# AVALON2_chip_21b.net
KiCad netlist of a schematic drawn in Altium Designer
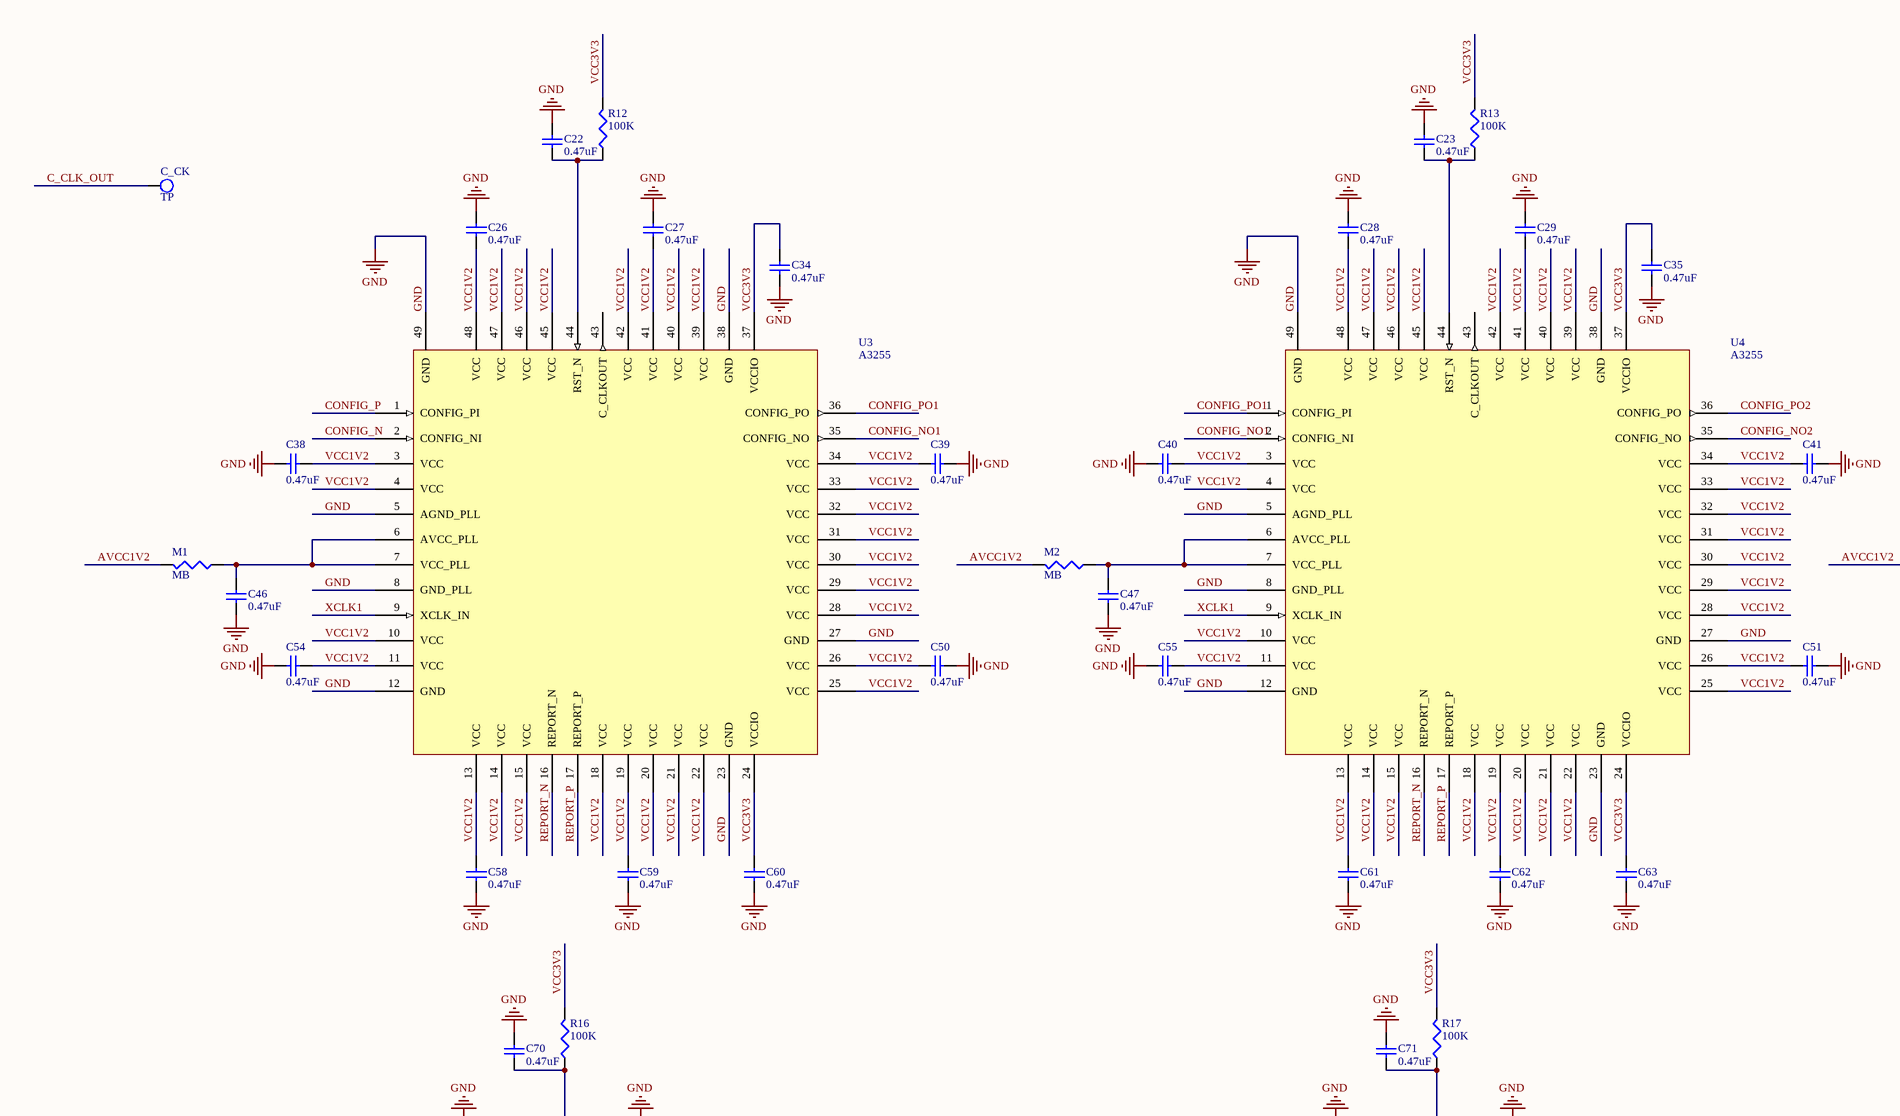
[diagram p0: AVALON2_chip_21b.SchDoc, top left]
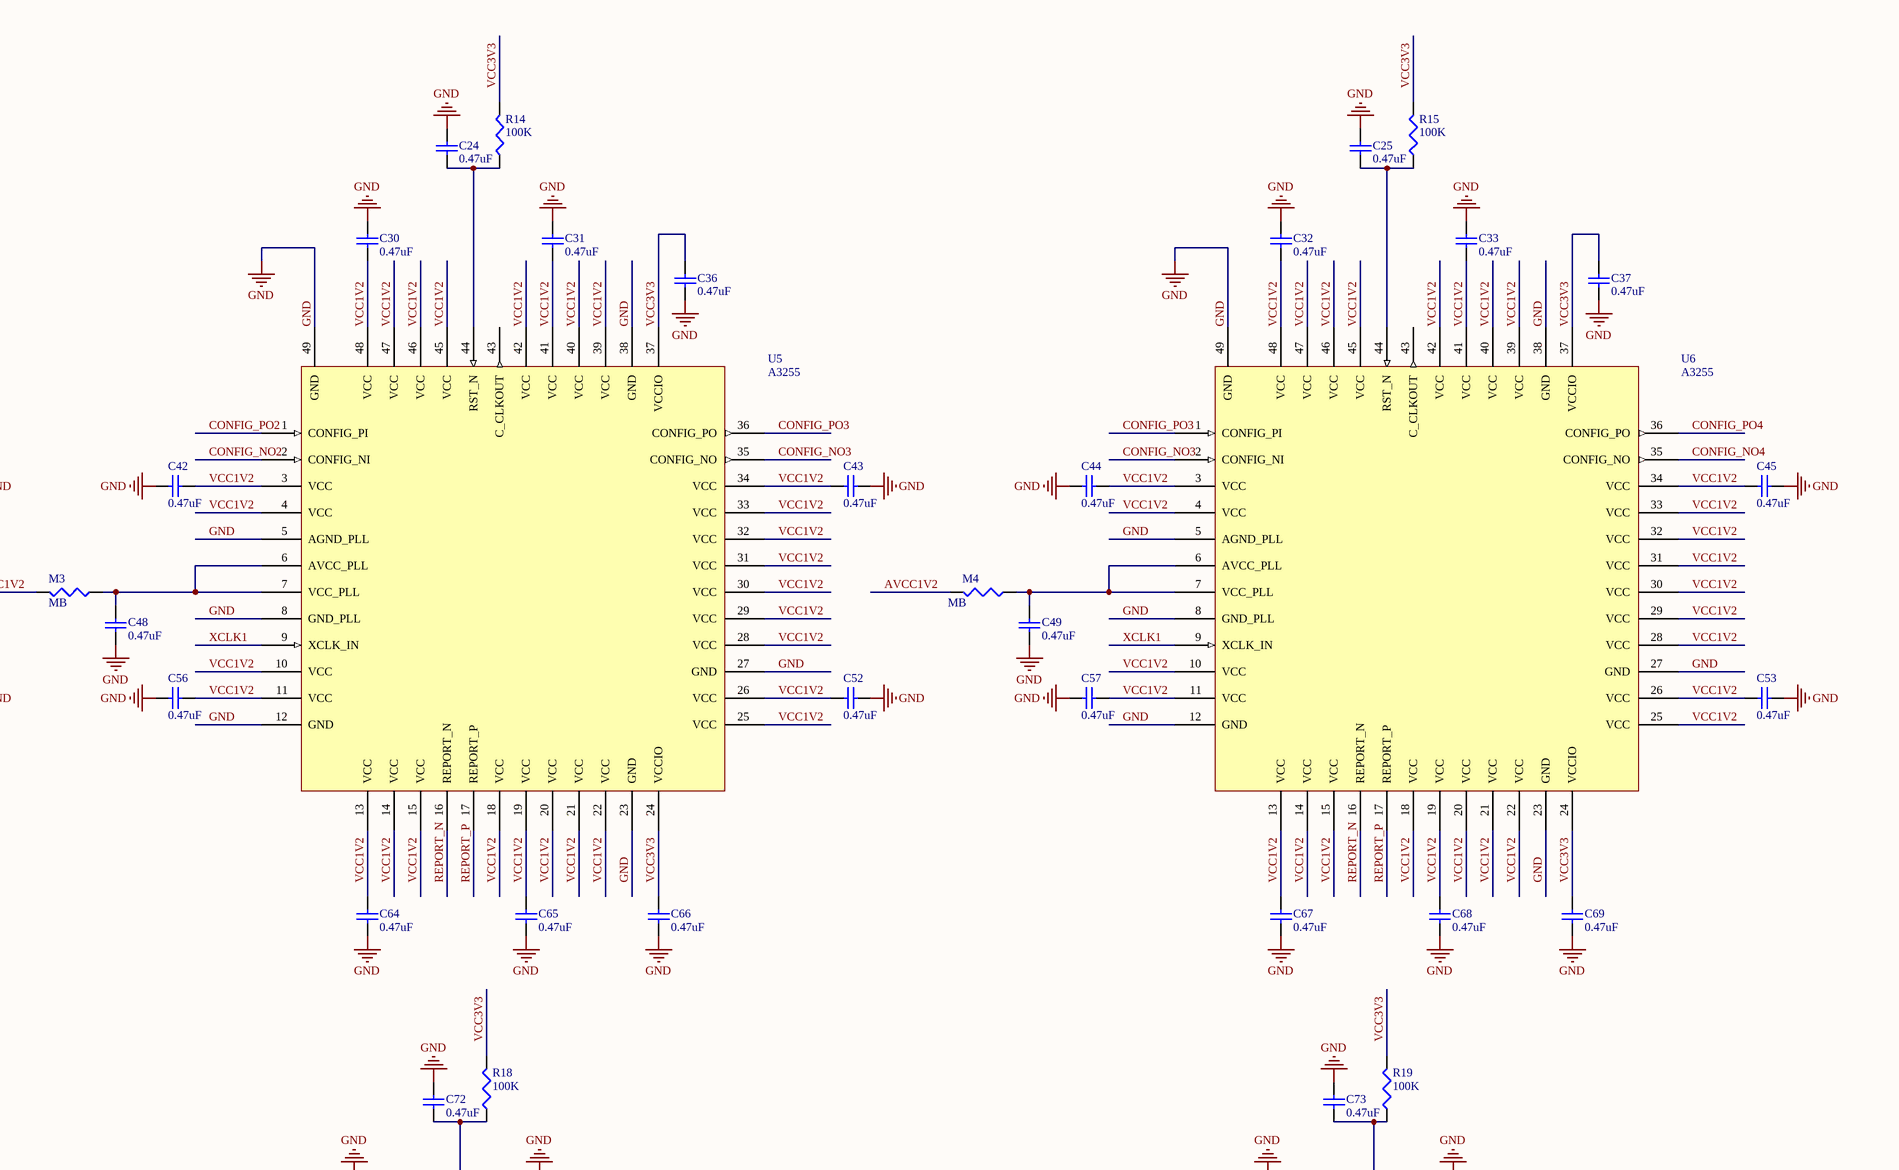
[diagram p1: AVALON2_chip_21b.SchDoc, top right]
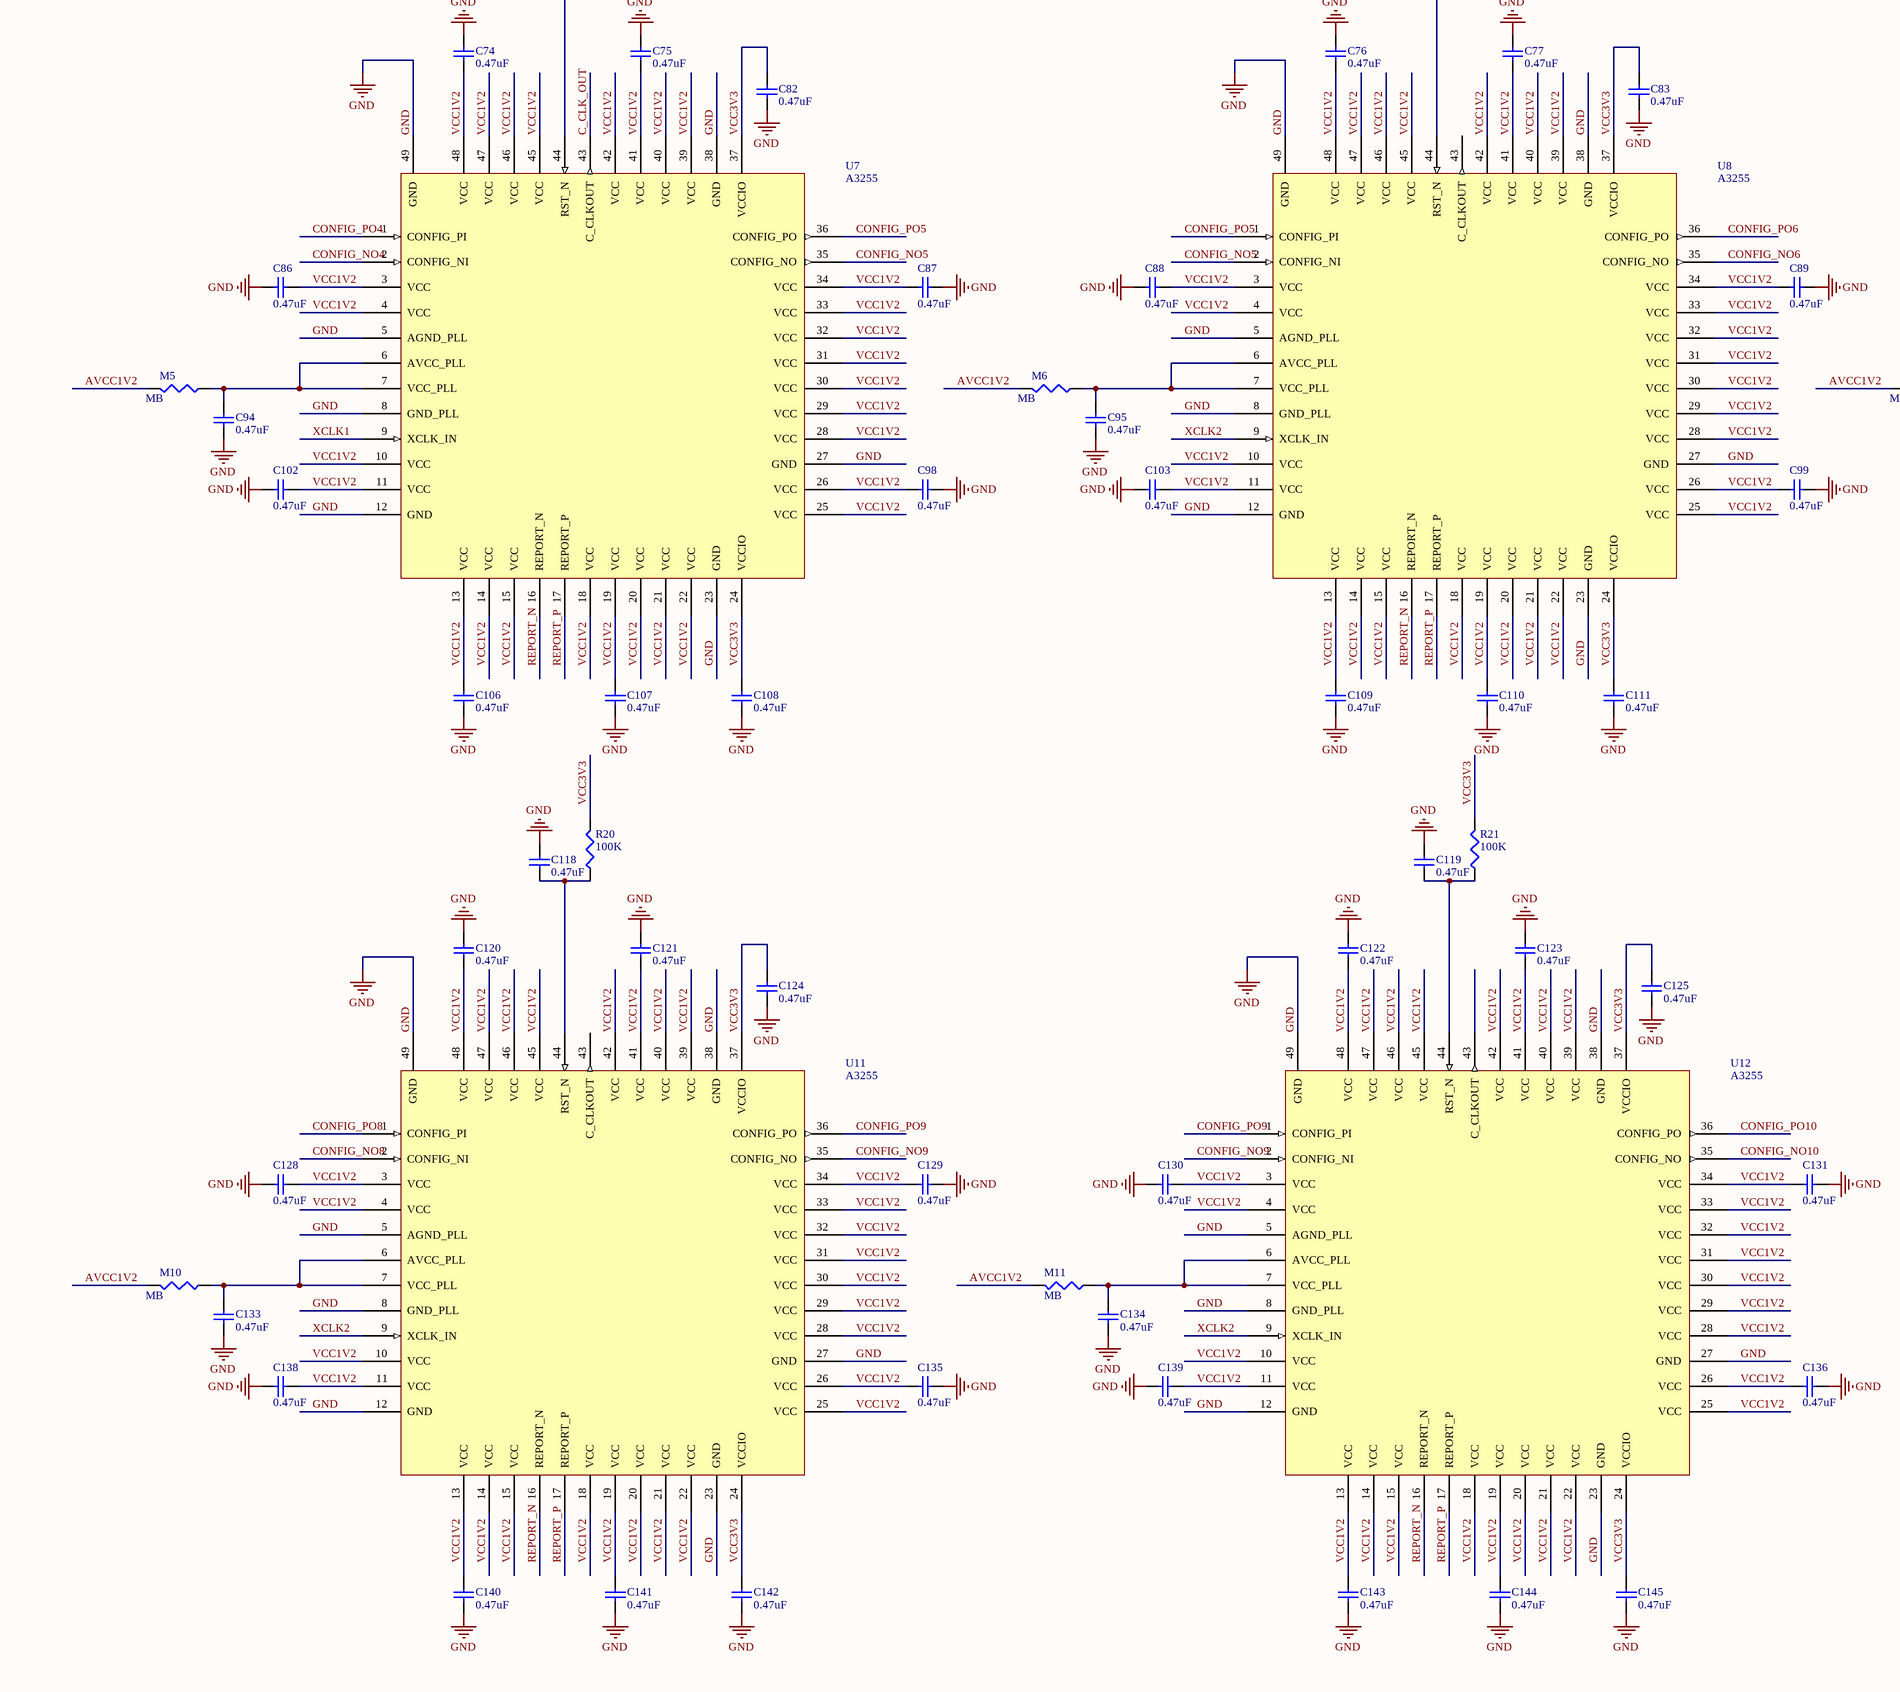
[diagram p2: AVALON2_chip_21b.SchDoc, bottom left]
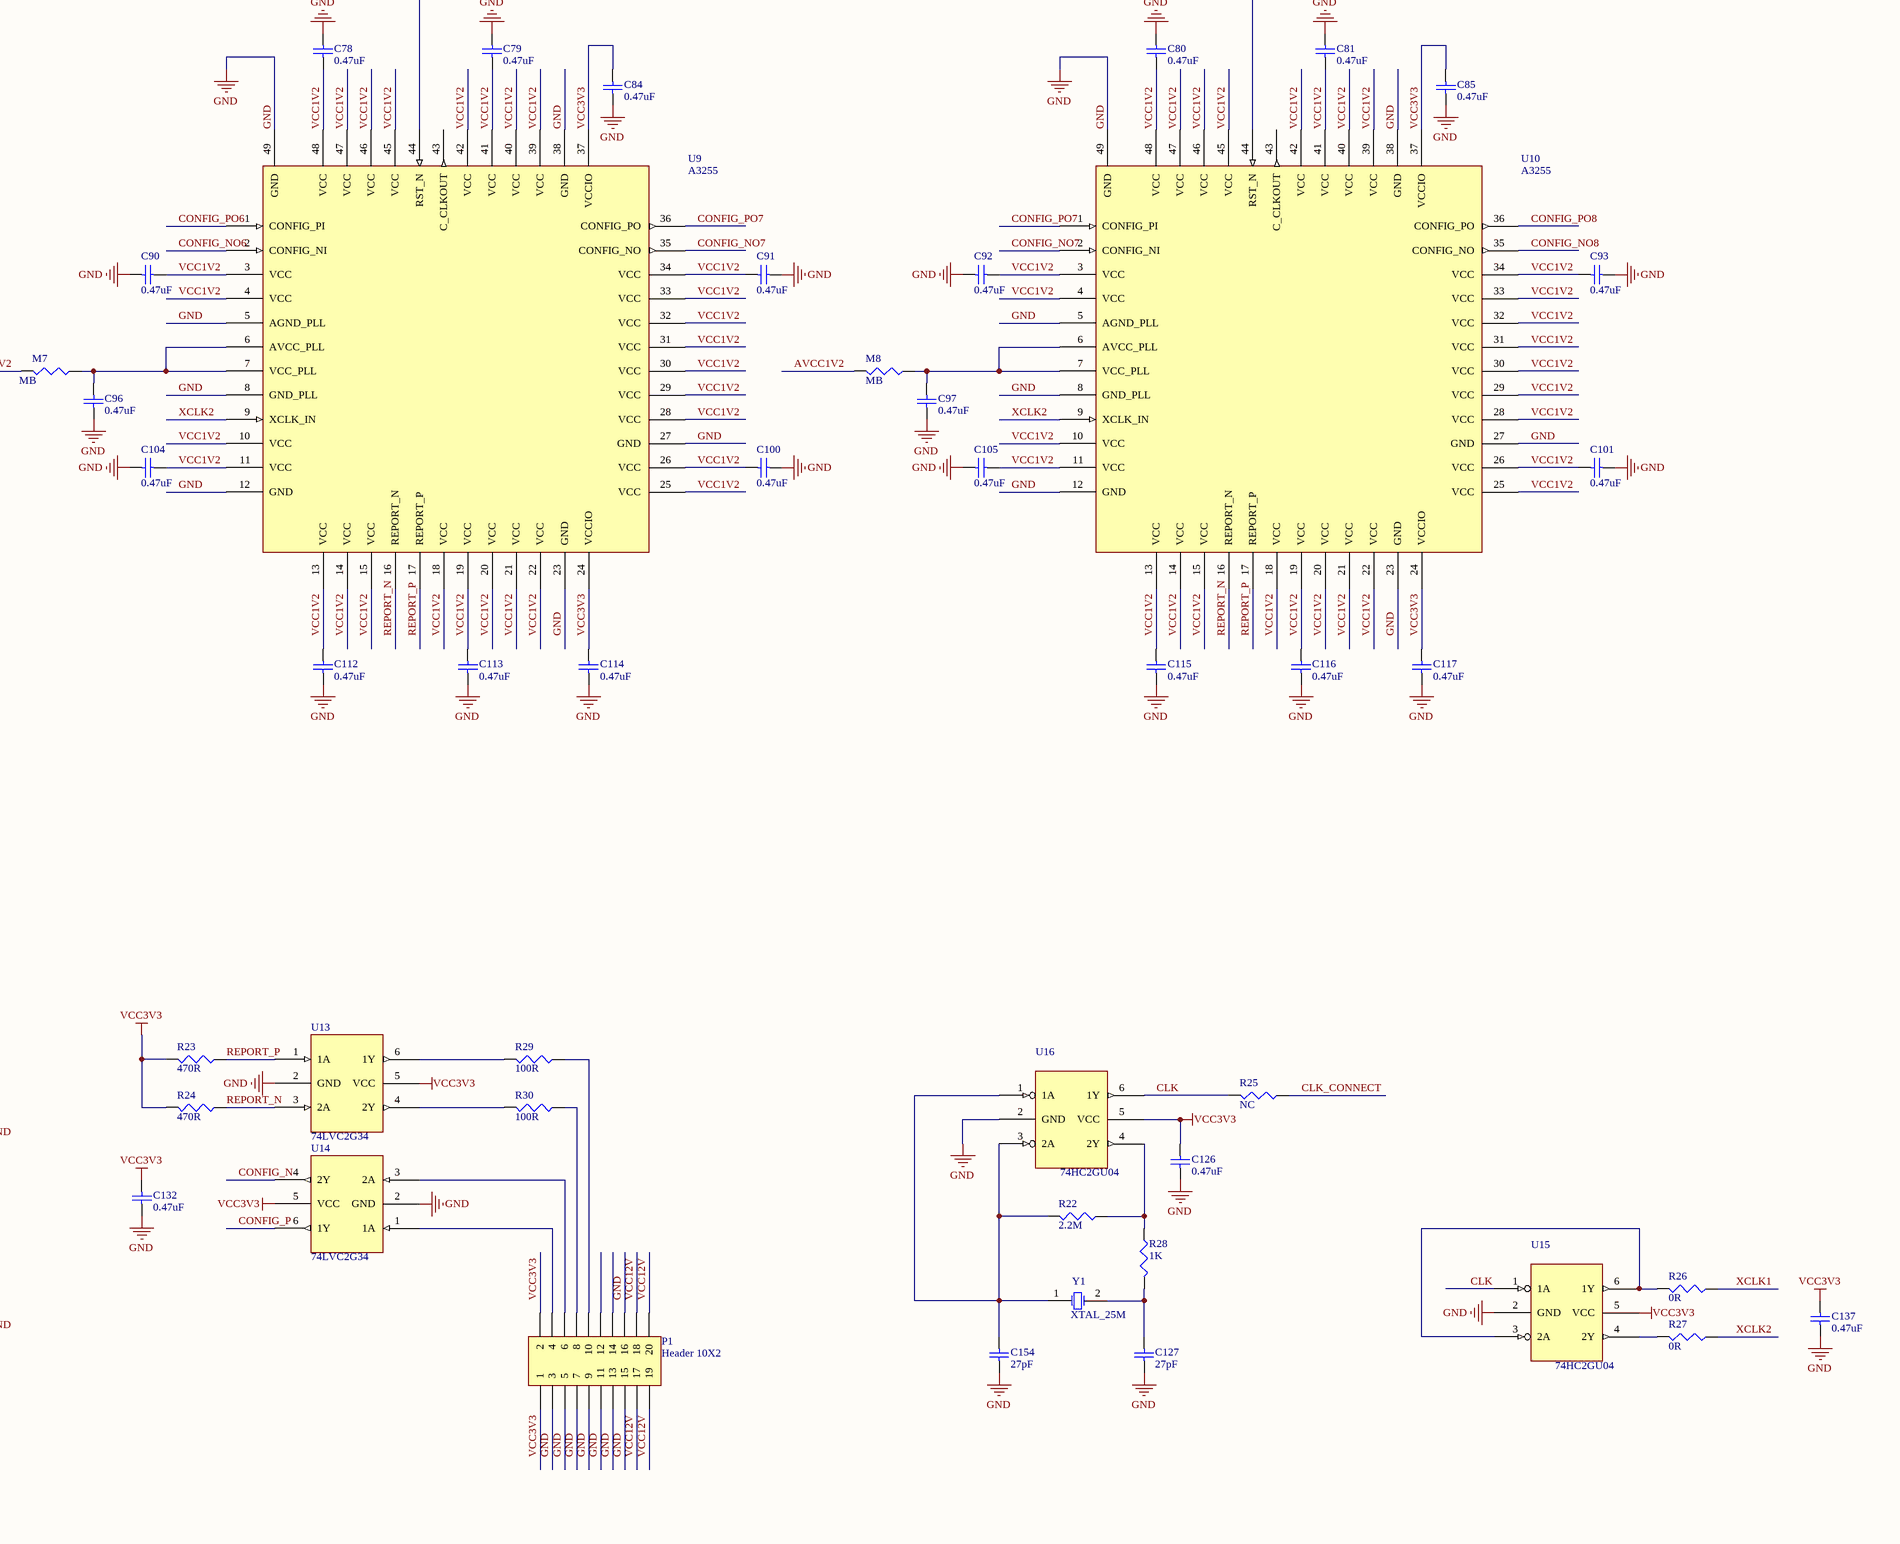
[diagram p3: AVALON2_chip_21b.SchDoc, bottom right]

(export (version "E")
  (design (tool "Eeschema 10.0.6"))
  (components
    (comp (ref "C22")
      (value "0.47uF")
      (footprint "CAPC1005L")
      (description "Capacitor (Semiconductor SIM Model)")
      (fields (field (name "PUBLISHER") "Altium Limited"))
      (libsource (lib "Miscellaneous Devices") (part "Cap Semi"))
    )
    (comp (ref "C23")
      (value "0.47uF")
      (footprint "CAPC1005L")
      (description "Capacitor (Semiconductor SIM Model)")
      (fields (field (name "PUBLISHER") "Altium Limited"))
      (libsource (lib "Miscellaneous Devices") (part "Cap Semi"))
    )
    (comp (ref "C24")
      (value "0.47uF")
      (footprint "CAPC1005L")
      (description "Capacitor (Semiconductor SIM Model)")
      (fields (field (name "PUBLISHER") "Altium Limited"))
      (libsource (lib "Miscellaneous Devices") (part "Cap Semi"))
    )
    (comp (ref "C25")
      (value "0.47uF")
      (footprint "CAPC1005L")
      (description "Capacitor (Semiconductor SIM Model)")
      (fields (field (name "PUBLISHER") "Altium Limited"))
      (libsource (lib "Miscellaneous Devices") (part "Cap Semi"))
    )
    (comp (ref "C26")
      (value "0.47uF")
      (footprint "CAPC1005L")
      (description "Capacitor (Semiconductor SIM Model)")
      (fields (field (name "PUBLISHER") "Altium Limited"))
      (libsource (lib "Miscellaneous Devices") (part "Cap Semi"))
    )
    (comp (ref "C27")
      (value "0.47uF")
      (footprint "CAPC1005L")
      (description "Capacitor (Semiconductor SIM Model)")
      (fields (field (name "PUBLISHER") "Altium Limited"))
      (libsource (lib "Miscellaneous Devices") (part "Cap Semi"))
    )
    (comp (ref "C28")
      (value "0.47uF")
      (footprint "CAPC1005L")
      (description "Capacitor (Semiconductor SIM Model)")
      (fields (field (name "PUBLISHER") "Altium Limited"))
      (libsource (lib "Miscellaneous Devices") (part "Cap Semi"))
    )
    (comp (ref "C29")
      (value "0.47uF")
      (footprint "CAPC1005L")
      (description "Capacitor (Semiconductor SIM Model)")
      (fields (field (name "PUBLISHER") "Altium Limited"))
      (libsource (lib "Miscellaneous Devices") (part "Cap Semi"))
    )
    (comp (ref "C30")
      (value "0.47uF")
      (footprint "CAPC1005L")
      (description "Capacitor (Semiconductor SIM Model)")
      (fields (field (name "PUBLISHER") "Altium Limited"))
      (libsource (lib "Miscellaneous Devices") (part "Cap Semi"))
    )
    (comp (ref "C31")
      (value "0.47uF")
      (footprint "CAPC1005L")
      (description "Capacitor (Semiconductor SIM Model)")
      (fields (field (name "PUBLISHER") "Altium Limited"))
      (libsource (lib "Miscellaneous Devices") (part "Cap Semi"))
    )
    (comp (ref "C32")
      (value "0.47uF")
      (footprint "CAPC1005L")
      (description "Capacitor (Semiconductor SIM Model)")
      (fields (field (name "PUBLISHER") "Altium Limited"))
      (libsource (lib "Miscellaneous Devices") (part "Cap Semi"))
    )
    (comp (ref "C33")
      (value "0.47uF")
      (footprint "CAPC1005L")
      (description "Capacitor (Semiconductor SIM Model)")
      (fields (field (name "PUBLISHER") "Altium Limited"))
      (libsource (lib "Miscellaneous Devices") (part "Cap Semi"))
    )
    (comp (ref "C34")
      (value "0.47uF")
      (footprint "CAPC1005L")
      (description "Capacitor (Semiconductor SIM Model)")
      (fields (field (name "PUBLISHER") "Altium Limited"))
      (libsource (lib "Miscellaneous Devices") (part "Cap Semi"))
    )
    (comp (ref "C35")
      (value "0.47uF")
      (footprint "CAPC1005L")
      (description "Capacitor (Semiconductor SIM Model)")
      (fields (field (name "PUBLISHER") "Altium Limited"))
      (libsource (lib "Miscellaneous Devices") (part "Cap Semi"))
    )
    (comp (ref "C36")
      (value "0.47uF")
      (footprint "CAPC1005L")
      (description "Capacitor (Semiconductor SIM Model)")
      (fields (field (name "PUBLISHER") "Altium Limited"))
      (libsource (lib "Miscellaneous Devices") (part "Cap Semi"))
    )
    (comp (ref "C37")
      (value "0.47uF")
      (footprint "CAPC1005L")
      (description "Capacitor (Semiconductor SIM Model)")
      (fields (field (name "PUBLISHER") "Altium Limited"))
      (libsource (lib "Miscellaneous Devices") (part "Cap Semi"))
    )
    (comp (ref "C38")
      (value "0.47uF")
      (footprint "CAPC1005L")
      (description "Capacitor (Semiconductor SIM Model)")
      (fields (field (name "PUBLISHER") "Altium Limited"))
      (libsource (lib "Miscellaneous Devices") (part "Cap Semi"))
    )
    (comp (ref "C39")
      (value "0.47uF")
      (footprint "CAPC1005L")
      (description "Capacitor (Semiconductor SIM Model)")
      (fields (field (name "PUBLISHER") "Altium Limited"))
      (libsource (lib "Miscellaneous Devices") (part "Cap Semi"))
    )
    (comp (ref "C40")
      (value "0.47uF")
      (footprint "CAPC1005L")
      (description "Capacitor (Semiconductor SIM Model)")
      (fields (field (name "PUBLISHER") "Altium Limited"))
      (libsource (lib "Miscellaneous Devices") (part "Cap Semi"))
    )
    (comp (ref "C41")
      (value "0.47uF")
      (footprint "CAPC1005L")
      (description "Capacitor (Semiconductor SIM Model)")
      (fields (field (name "PUBLISHER") "Altium Limited"))
      (libsource (lib "Miscellaneous Devices") (part "Cap Semi"))
    )
    (comp (ref "C42")
      (value "0.47uF")
      (footprint "CAPC1005L")
      (description "Capacitor (Semiconductor SIM Model)")
      (fields (field (name "PUBLISHER") "Altium Limited"))
      (libsource (lib "Miscellaneous Devices") (part "Cap Semi"))
    )
    (comp (ref "C43")
      (value "0.47uF")
      (footprint "CAPC1005L")
      (description "Capacitor (Semiconductor SIM Model)")
      (fields (field (name "PUBLISHER") "Altium Limited"))
      (libsource (lib "Miscellaneous Devices") (part "Cap Semi"))
    )
    (comp (ref "C44")
      (value "0.47uF")
      (footprint "CAPC1005L")
      (description "Capacitor (Semiconductor SIM Model)")
      (fields (field (name "PUBLISHER") "Altium Limited"))
      (libsource (lib "Miscellaneous Devices") (part "Cap Semi"))
    )
    (comp (ref "C45")
      (value "0.47uF")
      (footprint "CAPC1005L")
      (description "Capacitor (Semiconductor SIM Model)")
      (fields (field (name "PUBLISHER") "Altium Limited"))
      (libsource (lib "Miscellaneous Devices") (part "Cap Semi"))
    )
    (comp (ref "C46")
      (value "0.47uF")
      (footprint "CAPC1005L")
      (description "Capacitor (Semiconductor SIM Model)")
      (fields (field (name "PUBLISHER") "Altium Limited"))
      (libsource (lib "Miscellaneous Devices") (part "Cap Semi"))
    )
    (comp (ref "C47")
      (value "0.47uF")
      (footprint "CAPC1005L")
      (description "Capacitor (Semiconductor SIM Model)")
      (fields (field (name "PUBLISHER") "Altium Limited"))
      (libsource (lib "Miscellaneous Devices") (part "Cap Semi"))
    )
    (comp (ref "C48")
      (value "0.47uF")
      (footprint "CAPC1005L")
      (description "Capacitor (Semiconductor SIM Model)")
      (fields (field (name "PUBLISHER") "Altium Limited"))
      (libsource (lib "Miscellaneous Devices") (part "Cap Semi"))
    )
    (comp (ref "C49")
      (value "0.47uF")
      (footprint "CAPC1005L")
      (description "Capacitor (Semiconductor SIM Model)")
      (fields (field (name "PUBLISHER") "Altium Limited"))
      (libsource (lib "Miscellaneous Devices") (part "Cap Semi"))
    )
    (comp (ref "C50")
      (value "0.47uF")
      (footprint "CAPC1005L")
      (description "Capacitor (Semiconductor SIM Model)")
      (fields (field (name "PUBLISHER") "Altium Limited"))
      (libsource (lib "Miscellaneous Devices") (part "Cap Semi"))
    )
    (comp (ref "C51")
      (value "0.47uF")
      (footprint "CAPC1005L")
      (description "Capacitor (Semiconductor SIM Model)")
      (fields (field (name "PUBLISHER") "Altium Limited"))
      (libsource (lib "Miscellaneous Devices") (part "Cap Semi"))
    )
    (comp (ref "C52")
      (value "0.47uF")
      (footprint "CAPC1005L")
      (description "Capacitor (Semiconductor SIM Model)")
      (fields (field (name "PUBLISHER") "Altium Limited"))
      (libsource (lib "Miscellaneous Devices") (part "Cap Semi"))
    )
    (comp (ref "C53")
      (value "0.47uF")
      (footprint "CAPC1005L")
      (description "Capacitor (Semiconductor SIM Model)")
      (fields (field (name "PUBLISHER") "Altium Limited"))
      (libsource (lib "Miscellaneous Devices") (part "Cap Semi"))
    )
    (comp (ref "C54")
      (value "0.47uF")
      (footprint "CAPC1005L")
      (description "Capacitor (Semiconductor SIM Model)")
      (fields (field (name "PUBLISHER") "Altium Limited"))
      (libsource (lib "Miscellaneous Devices") (part "Cap Semi"))
    )
    (comp (ref "C55")
      (value "0.47uF")
      (footprint "CAPC1005L")
      (description "Capacitor (Semiconductor SIM Model)")
      (fields (field (name "PUBLISHER") "Altium Limited"))
      (libsource (lib "Miscellaneous Devices") (part "Cap Semi"))
    )
    (comp (ref "C56")
      (value "0.47uF")
      (footprint "CAPC1005L")
      (description "Capacitor (Semiconductor SIM Model)")
      (fields (field (name "PUBLISHER") "Altium Limited"))
      (libsource (lib "Miscellaneous Devices") (part "Cap Semi"))
    )
    (comp (ref "C57")
      (value "0.47uF")
      (footprint "CAPC1005L")
      (description "Capacitor (Semiconductor SIM Model)")
      (fields (field (name "PUBLISHER") "Altium Limited"))
      (libsource (lib "Miscellaneous Devices") (part "Cap Semi"))
    )
    (comp (ref "C58")
      (value "0.47uF")
      (footprint "CAPC1005L")
      (description "Capacitor (Semiconductor SIM Model)")
      (fields (field (name "PUBLISHER") "Altium Limited"))
      (libsource (lib "Miscellaneous Devices") (part "Cap Semi"))
    )
    (comp (ref "C59")
      (value "0.47uF")
      (footprint "CAPC1005L")
      (description "Capacitor (Semiconductor SIM Model)")
      (fields (field (name "PUBLISHER") "Altium Limited"))
      (libsource (lib "Miscellaneous Devices") (part "Cap Semi"))
    )
    (comp (ref "C60")
      (value "0.47uF")
      (footprint "CAPC1005L")
      (description "Capacitor (Semiconductor SIM Model)")
      (fields (field (name "PUBLISHER") "Altium Limited"))
      (libsource (lib "Miscellaneous Devices") (part "Cap Semi"))
    )
    (comp (ref "C61")
      (value "0.47uF")
      (footprint "CAPC1005L")
      (description "Capacitor (Semiconductor SIM Model)")
      (fields (field (name "PUBLISHER") "Altium Limited"))
      (libsource (lib "Miscellaneous Devices") (part "Cap Semi"))
    )
    (comp (ref "C62")
      (value "0.47uF")
      (footprint "CAPC1005L")
      (description "Capacitor (Semiconductor SIM Model)")
      (fields (field (name "PUBLISHER") "Altium Limited"))
      (libsource (lib "Miscellaneous Devices") (part "Cap Semi"))
    )
    (comp (ref "C63")
      (value "0.47uF")
      (footprint "CAPC1005L")
      (description "Capacitor (Semiconductor SIM Model)")
      (fields (field (name "PUBLISHER") "Altium Limited"))
      (libsource (lib "Miscellaneous Devices") (part "Cap Semi"))
    )
    (comp (ref "C64")
      (value "0.47uF")
      (footprint "CAPC1005L")
      (description "Capacitor (Semiconductor SIM Model)")
      (fields (field (name "PUBLISHER") "Altium Limited"))
      (libsource (lib "Miscellaneous Devices") (part "Cap Semi"))
    )
    (comp (ref "C65")
      (value "0.47uF")
      (footprint "CAPC1005L")
      (description "Capacitor (Semiconductor SIM Model)")
      (fields (field (name "PUBLISHER") "Altium Limited"))
      (libsource (lib "Miscellaneous Devices") (part "Cap Semi"))
    )
    (comp (ref "C66")
      (value "0.47uF")
      (footprint "CAPC1005L")
      (description "Capacitor (Semiconductor SIM Model)")
      (fields (field (name "PUBLISHER") "Altium Limited"))
      (libsource (lib "Miscellaneous Devices") (part "Cap Semi"))
    )
    (comp (ref "C67")
      (value "0.47uF")
      (footprint "CAPC1005L")
      (description "Capacitor (Semiconductor SIM Model)")
      (fields (field (name "PUBLISHER") "Altium Limited"))
      (libsource (lib "Miscellaneous Devices") (part "Cap Semi"))
    )
    (comp (ref "C68")
      (value "0.47uF")
      (footprint "CAPC1005L")
      (description "Capacitor (Semiconductor SIM Model)")
      (fields (field (name "PUBLISHER") "Altium Limited"))
      (libsource (lib "Miscellaneous Devices") (part "Cap Semi"))
    )
    (comp (ref "C69")
      (value "0.47uF")
      (footprint "CAPC1005L")
      (description "Capacitor (Semiconductor SIM Model)")
      (fields (field (name "PUBLISHER") "Altium Limited"))
      (libsource (lib "Miscellaneous Devices") (part "Cap Semi"))
    )
    (comp (ref "C70")
      (value "0.47uF")
      (footprint "CAPC1005L")
      (description "Capacitor (Semiconductor SIM Model)")
      (fields (field (name "PUBLISHER") "Altium Limited"))
      (libsource (lib "Miscellaneous Devices") (part "Cap Semi"))
    )
    (comp (ref "C71")
      (value "0.47uF")
      (footprint "CAPC1005L")
      (description "Capacitor (Semiconductor SIM Model)")
      (fields (field (name "PUBLISHER") "Altium Limited"))
      (libsource (lib "Miscellaneous Devices") (part "Cap Semi"))
    )
    (comp (ref "C72")
      (value "0.47uF")
      (footprint "CAPC1005L")
      (description "Capacitor (Semiconductor SIM Model)")
      (fields (field (name "PUBLISHER") "Altium Limited"))
      (libsource (lib "Miscellaneous Devices") (part "Cap Semi"))
    )
    (comp (ref "C73")
      (value "0.47uF")
      (footprint "CAPC1005L")
      (description "Capacitor (Semiconductor SIM Model)")
      (fields (field (name "PUBLISHER") "Altium Limited"))
      (libsource (lib "Miscellaneous Devices") (part "Cap Semi"))
    )
    (comp (ref "C74")
      (value "0.47uF")
      (footprint "CAPC1005L")
      (description "Capacitor (Semiconductor SIM Model)")
      (fields (field (name "PUBLISHER") "Altium Limited"))
      (libsource (lib "Miscellaneous Devices") (part "Cap Semi"))
    )
    (comp (ref "C75")
      (value "0.47uF")
      (footprint "CAPC1005L")
      (description "Capacitor (Semiconductor SIM Model)")
      (fields (field (name "PUBLISHER") "Altium Limited"))
      (libsource (lib "Miscellaneous Devices") (part "Cap Semi"))
    )
    (comp (ref "C76")
      (value "0.47uF")
      (footprint "CAPC1005L")
      (description "Capacitor (Semiconductor SIM Model)")
      (fields (field (name "PUBLISHER") "Altium Limited"))
      (libsource (lib "Miscellaneous Devices") (part "Cap Semi"))
    )
    (comp (ref "C77")
      (value "0.47uF")
      (footprint "CAPC1005L")
      (description "Capacitor (Semiconductor SIM Model)")
      (fields (field (name "PUBLISHER") "Altium Limited"))
      (libsource (lib "Miscellaneous Devices") (part "Cap Semi"))
    )
    (comp (ref "C78")
      (value "0.47uF")
      (footprint "CAPC1005L")
      (description "Capacitor (Semiconductor SIM Model)")
      (fields (field (name "PUBLISHER") "Altium Limited"))
      (libsource (lib "Miscellaneous Devices") (part "Cap Semi"))
    )
    (comp (ref "C79")
      (value "0.47uF")
      (footprint "CAPC1005L")
      (description "Capacitor (Semiconductor SIM Model)")
      (fields (field (name "PUBLISHER") "Altium Limited"))
      (libsource (lib "Miscellaneous Devices") (part "Cap Semi"))
    )
    (comp (ref "C80")
      (value "0.47uF")
      (footprint "CAPC1005L")
      (description "Capacitor (Semiconductor SIM Model)")
      (fields (field (name "PUBLISHER") "Altium Limited"))
      (libsource (lib "Miscellaneous Devices") (part "Cap Semi"))
    )
    (comp (ref "C81")
      (value "0.47uF")
      (footprint "CAPC1005L")
      (description "Capacitor (Semiconductor SIM Model)")
      (fields (field (name "PUBLISHER") "Altium Limited"))
      (libsource (lib "Miscellaneous Devices") (part "Cap Semi"))
    )
    (comp (ref "C82")
      (value "0.47uF")
      (footprint "CAPC1005L")
      (description "Capacitor (Semiconductor SIM Model)")
      (fields (field (name "PUBLISHER") "Altium Limited"))
      (libsource (lib "Miscellaneous Devices") (part "Cap Semi"))
    )
    (comp (ref "C83")
      (value "0.47uF")
      (footprint "CAPC1005L")
      (description "Capacitor (Semiconductor SIM Model)")
      (fields (field (name "PUBLISHER") "Altium Limited"))
      (libsource (lib "Miscellaneous Devices") (part "Cap Semi"))
    )
    (comp (ref "C84")
      (value "0.47uF")
      (footprint "CAPC1005L")
      (description "Capacitor (Semiconductor SIM Model)")
      (fields (field (name "PUBLISHER") "Altium Limited"))
      (libsource (lib "Miscellaneous Devices") (part "Cap Semi"))
    )
    (comp (ref "C85")
      (value "0.47uF")
      (footprint "CAPC1005L")
      (description "Capacitor (Semiconductor SIM Model)")
      (fields (field (name "PUBLISHER") "Altium Limited"))
      (libsource (lib "Miscellaneous Devices") (part "Cap Semi"))
    )
    (comp (ref "C86")
      (value "0.47uF")
      (footprint "CAPC1005L")
      (description "Capacitor (Semiconductor SIM Model)")
      (fields (field (name "PUBLISHER") "Altium Limited"))
      (libsource (lib "Miscellaneous Devices") (part "Cap Semi"))
    )
    (comp (ref "C87")
      (value "0.47uF")
      (footprint "CAPC1005L")
      (description "Capacitor (Semiconductor SIM Model)")
      (fields (field (name "PUBLISHER") "Altium Limited"))
      (libsource (lib "Miscellaneous Devices") (part "Cap Semi"))
    )
    (comp (ref "C88")
      (value "0.47uF")
      (footprint "CAPC1005L")
      (description "Capacitor (Semiconductor SIM Model)")
      (fields (field (name "PUBLISHER") "Altium Limited"))
      (libsource (lib "Miscellaneous Devices") (part "Cap Semi"))
    )
    (comp (ref "C89")
      (value "0.47uF")
      (footprint "CAPC1005L")
      (description "Capacitor (Semiconductor SIM Model)")
      (fields (field (name "PUBLISHER") "Altium Limited"))
      (libsource (lib "Miscellaneous Devices") (part "Cap Semi"))
    )
    (comp (ref "C90")
      (value "0.47uF")
      (footprint "CAPC1005L")
      (description "Capacitor (Semiconductor SIM Model)")
      (fields (field (name "PUBLISHER") "Altium Limited"))
      (libsource (lib "Miscellaneous Devices") (part "Cap Semi"))
    )
    (comp (ref "C91")
      (value "0.47uF")
      (footprint "CAPC1005L")
      (description "Capacitor (Semiconductor SIM Model)")
      (fields (field (name "PUBLISHER") "Altium Limited"))
      (libsource (lib "Miscellaneous Devices") (part "Cap Semi"))
    )
    (comp (ref "C92")
      (value "0.47uF")
      (footprint "CAPC1005L")
      (description "Capacitor (Semiconductor SIM Model)")
      (fields (field (name "PUBLISHER") "Altium Limited"))
      (libsource (lib "Miscellaneous Devices") (part "Cap Semi"))
    )
    (comp (ref "C93")
      (value "0.47uF")
      (footprint "CAPC1005L")
      (description "Capacitor (Semiconductor SIM Model)")
      (fields (field (name "PUBLISHER") "Altium Limited"))
      (libsource (lib "Miscellaneous Devices") (part "Cap Semi"))
    )
    (comp (ref "C94")
      (value "0.47uF")
      (footprint "CAPC1005L")
      (description "Capacitor (Semiconductor SIM Model)")
      (fields (field (name "PUBLISHER") "Altium Limited"))
      (libsource (lib "Miscellaneous Devices") (part "Cap Semi"))
    )
    (comp (ref "C95")
      (value "0.47uF")
      (footprint "CAPC1005L")
      (description "Capacitor (Semiconductor SIM Model)")
      (fields (field (name "PUBLISHER") "Altium Limited"))
      (libsource (lib "Miscellaneous Devices") (part "Cap Semi"))
    )
    (comp (ref "C96")
      (value "0.47uF")
      (footprint "CAPC1005L")
      (description "Capacitor (Semiconductor SIM Model)")
      (fields (field (name "PUBLISHER") "Altium Limited"))
      (libsource (lib "Miscellaneous Devices") (part "Cap Semi"))
    )
    (comp (ref "C97")
      (value "0.47uF")
      (footprint "CAPC1005L")
      (description "Capacitor (Semiconductor SIM Model)")
      (fields (field (name "PUBLISHER") "Altium Limited"))
      (libsource (lib "Miscellaneous Devices") (part "Cap Semi"))
    )
    (comp (ref "C98")
      (value "0.47uF")
      (footprint "CAPC1005L")
      (description "Capacitor (Semiconductor SIM Model)")
      (fields (field (name "PUBLISHER") "Altium Limited"))
      (libsource (lib "Miscellaneous Devices") (part "Cap Semi"))
    )
    (comp (ref "C99")
      (value "0.47uF")
      (footprint "CAPC1005L")
      (description "Capacitor (Semiconductor SIM Model)")
      (fields (field (name "PUBLISHER") "Altium Limited"))
      (libsource (lib "Miscellaneous Devices") (part "Cap Semi"))
    )
    (comp (ref "C100")
      (value "0.47uF")
      (footprint "CAPC1005L")
      (description "Capacitor (Semiconductor SIM Model)")
      (fields (field (name "PUBLISHER") "Altium Limited"))
      (libsource (lib "Miscellaneous Devices") (part "Cap Semi"))
    )
    (comp (ref "C101")
      (value "0.47uF")
      (footprint "CAPC1005L")
      (description "Capacitor (Semiconductor SIM Model)")
      (fields (field (name "PUBLISHER") "Altium Limited"))
      (libsource (lib "Miscellaneous Devices") (part "Cap Semi"))
    )
    (comp (ref "C102")
      (value "0.47uF")
      (footprint "CAPC1005L")
      (description "Capacitor (Semiconductor SIM Model)")
      (fields (field (name "PUBLISHER") "Altium Limited"))
      (libsource (lib "Miscellaneous Devices") (part "Cap Semi"))
    )
    (comp (ref "C103")
      (value "0.47uF")
      (footprint "CAPC1005L")
      (description "Capacitor (Semiconductor SIM Model)")
      (fields (field (name "PUBLISHER") "Altium Limited"))
      (libsource (lib "Miscellaneous Devices") (part "Cap Semi"))
    )
    (comp (ref "C104")
      (value "0.47uF")
      (footprint "CAPC1005L")
      (description "Capacitor (Semiconductor SIM Model)")
      (fields (field (name "PUBLISHER") "Altium Limited"))
      (libsource (lib "Miscellaneous Devices") (part "Cap Semi"))
    )
    (comp (ref "C105")
      (value "0.47uF")
      (footprint "CAPC1005L")
      (description "Capacitor (Semiconductor SIM Model)")
      (fields (field (name "PUBLISHER") "Altium Limited"))
      (libsource (lib "Miscellaneous Devices") (part "Cap Semi"))
    )
    (comp (ref "C106")
      (value "0.47uF")
      (footprint "CAPC1005L")
      (description "Capacitor (Semiconductor SIM Model)")
      (fields (field (name "PUBLISHER") "Altium Limited"))
      (libsource (lib "Miscellaneous Devices") (part "Cap Semi"))
    )
    (comp (ref "C107")
      (value "0.47uF")
      (footprint "CAPC1005L")
      (description "Capacitor (Semiconductor SIM Model)")
      (fields (field (name "PUBLISHER") "Altium Limited"))
      (libsource (lib "Miscellaneous Devices") (part "Cap Semi"))
    )
    (comp (ref "C108")
      (value "0.47uF")
      (footprint "CAPC1005L")
      (description "Capacitor (Semiconductor SIM Model)")
      (fields (field (name "PUBLISHER") "Altium Limited"))
      (libsource (lib "Miscellaneous Devices") (part "Cap Semi"))
    )
    (comp (ref "C109")
      (value "0.47uF")
      (footprint "CAPC1005L")
      (description "Capacitor (Semiconductor SIM Model)")
      (fields (field (name "PUBLISHER") "Altium Limited"))
      (libsource (lib "Miscellaneous Devices") (part "Cap Semi"))
    )
    (comp (ref "C110")
      (value "0.47uF")
      (footprint "CAPC1005L")
      (description "Capacitor (Semiconductor SIM Model)")
      (fields (field (name "PUBLISHER") "Altium Limited"))
      (libsource (lib "Miscellaneous Devices") (part "Cap Semi"))
    )
    (comp (ref "C111")
      (value "0.47uF")
      (footprint "CAPC1005L")
      (description "Capacitor (Semiconductor SIM Model)")
      (fields (field (name "PUBLISHER") "Altium Limited"))
      (libsource (lib "Miscellaneous Devices") (part "Cap Semi"))
    )
    (comp (ref "C112")
      (value "0.47uF")
      (footprint "CAPC1005L")
      (description "Capacitor (Semiconductor SIM Model)")
      (fields (field (name "PUBLISHER") "Altium Limited"))
      (libsource (lib "Miscellaneous Devices") (part "Cap Semi"))
    )
    (comp (ref "C113")
      (value "0.47uF")
      (footprint "CAPC1005L")
      (description "Capacitor (Semiconductor SIM Model)")
      (fields (field (name "PUBLISHER") "Altium Limited"))
      (libsource (lib "Miscellaneous Devices") (part "Cap Semi"))
    )
    (comp (ref "C114")
      (value "0.47uF")
      (footprint "CAPC1005L")
      (description "Capacitor (Semiconductor SIM Model)")
      (fields (field (name "PUBLISHER") "Altium Limited"))
      (libsource (lib "Miscellaneous Devices") (part "Cap Semi"))
    )
    (comp (ref "C115")
      (value "0.47uF")
      (footprint "CAPC1005L")
      (description "Capacitor (Semiconductor SIM Model)")
      (fields (field (name "PUBLISHER") "Altium Limited"))
      (libsource (lib "Miscellaneous Devices") (part "Cap Semi"))
    )
    (comp (ref "C116")
      (value "0.47uF")
      (footprint "CAPC1005L")
      (description "Capacitor (Semiconductor SIM Model)")
      (fields (field (name "PUBLISHER") "Altium Limited"))
      (libsource (lib "Miscellaneous Devices") (part "Cap Semi"))
    )
    (comp (ref "C117")
      (value "0.47uF")
      (footprint "CAPC1005L")
      (description "Capacitor (Semiconductor SIM Model)")
      (fields (field (name "PUBLISHER") "Altium Limited"))
      (libsource (lib "Miscellaneous Devices") (part "Cap Semi"))
    )
    (comp (ref "C118")
      (value "0.47uF")
      (footprint "CAPC1005L")
      (description "Capacitor (Semiconductor SIM Model)")
      (fields (field (name "PUBLISHER") "Altium Limited"))
      (libsource (lib "Miscellaneous Devices") (part "Cap Semi"))
    )
    (comp (ref "C119")
      (value "0.47uF")
      (footprint "CAPC1005L")
      (description "Capacitor (Semiconductor SIM Model)")
      (fields (field (name "PUBLISHER") "Altium Limited"))
      (libsource (lib "Miscellaneous Devices") (part "Cap Semi"))
    )
    (comp (ref "C120")
      (value "0.47uF")
      (footprint "CAPC1005L")
      (description "Capacitor (Semiconductor SIM Model)")
      (fields (field (name "PUBLISHER") "Altium Limited"))
      (libsource (lib "Miscellaneous Devices") (part "Cap Semi"))
    )
    (comp (ref "C121")
      (value "0.47uF")
      (footprint "CAPC1005L")
      (description "Capacitor (Semiconductor SIM Model)")
      (fields (field (name "PUBLISHER") "Altium Limited"))
      (libsource (lib "Miscellaneous Devices") (part "Cap Semi"))
    )
    (comp (ref "C122")
      (value "0.47uF")
      (footprint "CAPC1005L")
      (description "Capacitor (Semiconductor SIM Model)")
      (fields (field (name "PUBLISHER") "Altium Limited"))
      (libsource (lib "Miscellaneous Devices") (part "Cap Semi"))
    )
    (comp (ref "C123")
      (value "0.47uF")
      (footprint "CAPC1005L")
      (description "Capacitor (Semiconductor SIM Model)")
      (fields (field (name "PUBLISHER") "Altium Limited"))
      (libsource (lib "Miscellaneous Devices") (part "Cap Semi"))
    )
    (comp (ref "C124")
      (value "0.47uF")
      (footprint "CAPC1005L")
      (description "Capacitor (Semiconductor SIM Model)")
      (fields (field (name "PUBLISHER") "Altium Limited"))
      (libsource (lib "Miscellaneous Devices") (part "Cap Semi"))
    )
    (comp (ref "C125")
      (value "0.47uF")
      (footprint "CAPC1005L")
      (description "Capacitor (Semiconductor SIM Model)")
      (fields (field (name "PUBLISHER") "Altium Limited"))
      (libsource (lib "Miscellaneous Devices") (part "Cap Semi"))
    )
    (comp (ref "C126")
      (value "0.47uF")
      (footprint "CAPC1005L")
      (description "Capacitor (Semiconductor SIM Model)")
      (fields (field (name "PUBLISHER") "Altium Limited"))
      (libsource (lib "Miscellaneous Devices") (part "Cap Semi"))
    )
    (comp (ref "C127")
      (value "27pF")
      (footprint "CAPC1005L")
      (description "Capacitor (Semiconductor SIM Model)")
      (fields (field (name "PUBLISHER") "Altium Limited"))
      (libsource (lib "Miscellaneous Devices") (part "Cap Semi"))
    )
    (comp (ref "C128")
      (value "0.47uF")
      (footprint "CAPC1005L")
      (description "Capacitor (Semiconductor SIM Model)")
      (fields (field (name "PUBLISHER") "Altium Limited"))
      (libsource (lib "Miscellaneous Devices") (part "Cap Semi"))
    )
    (comp (ref "C129")
      (value "0.47uF")
      (footprint "CAPC1005L")
      (description "Capacitor (Semiconductor SIM Model)")
      (fields (field (name "PUBLISHER") "Altium Limited"))
      (libsource (lib "Miscellaneous Devices") (part "Cap Semi"))
    )
    (comp (ref "C130")
      (value "0.47uF")
      (footprint "CAPC1005L")
      (description "Capacitor (Semiconductor SIM Model)")
      (fields (field (name "PUBLISHER") "Altium Limited"))
      (libsource (lib "Miscellaneous Devices") (part "Cap Semi"))
    )
    (comp (ref "C131")
      (value "0.47uF")
      (footprint "CAPC1005L")
      (description "Capacitor (Semiconductor SIM Model)")
      (fields (field (name "PUBLISHER") "Altium Limited"))
      (libsource (lib "Miscellaneous Devices") (part "Cap Semi"))
    )
    (comp (ref "C132")
      (value "0.47uF")
      (footprint "CAPC1005L")
      (description "Capacitor (Semiconductor SIM Model)")
      (fields (field (name "PUBLISHER") "Altium Limited"))
      (libsource (lib "Miscellaneous Devices") (part "Cap Semi"))
    )
    (comp (ref "C133")
      (value "0.47uF")
      (footprint "CAPC1005L")
      (description "Capacitor (Semiconductor SIM Model)")
      (fields (field (name "PUBLISHER") "Altium Limited"))
      (libsource (lib "Miscellaneous Devices") (part "Cap Semi"))
    )
    (comp (ref "C134")
      (value "0.47uF")
      (footprint "CAPC1005L")
      (description "Capacitor (Semiconductor SIM Model)")
      (fields (field (name "PUBLISHER") "Altium Limited"))
      (libsource (lib "Miscellaneous Devices") (part "Cap Semi"))
    )
    (comp (ref "C135")
      (value "0.47uF")
      (footprint "CAPC1005L")
      (description "Capacitor (Semiconductor SIM Model)")
      (fields (field (name "PUBLISHER") "Altium Limited"))
      (libsource (lib "Miscellaneous Devices") (part "Cap Semi"))
    )
    (comp (ref "C136")
      (value "0.47uF")
      (footprint "CAPC1005L")
      (description "Capacitor (Semiconductor SIM Model)")
      (fields (field (name "PUBLISHER") "Altium Limited"))
      (libsource (lib "Miscellaneous Devices") (part "Cap Semi"))
    )
    (comp (ref "C137")
      (value "0.47uF")
      (footprint "IPC-7352 Chip_Capacitor_L:CAPC1005L")
      (description "Capacitor (Semiconductor SIM Model)")
      (fields (field (name "PUBLISHER") "Altium Limited"))
      (libsource (lib "Miscellaneous Devices") (part "Cap Semi"))
    )
    (comp (ref "C138")
      (value "0.47uF")
      (footprint "CAPC1005L")
      (description "Capacitor (Semiconductor SIM Model)")
      (fields (field (name "PUBLISHER") "Altium Limited"))
      (libsource (lib "Miscellaneous Devices") (part "Cap Semi"))
    )
    (comp (ref "C139")
      (value "0.47uF")
      (footprint "CAPC1005L")
      (description "Capacitor (Semiconductor SIM Model)")
      (fields (field (name "PUBLISHER") "Altium Limited"))
      (libsource (lib "Miscellaneous Devices") (part "Cap Semi"))
    )
    (comp (ref "C140")
      (value "0.47uF")
      (footprint "CAPC1005L")
      (description "Capacitor (Semiconductor SIM Model)")
      (fields (field (name "PUBLISHER") "Altium Limited"))
      (libsource (lib "Miscellaneous Devices") (part "Cap Semi"))
    )
    (comp (ref "C141")
      (value "0.47uF")
      (footprint "CAPC1005L")
      (description "Capacitor (Semiconductor SIM Model)")
      (fields (field (name "PUBLISHER") "Altium Limited"))
      (libsource (lib "Miscellaneous Devices") (part "Cap Semi"))
    )
    (comp (ref "C142")
      (value "0.47uF")
      (footprint "CAPC1005L")
      (description "Capacitor (Semiconductor SIM Model)")
      (fields (field (name "PUBLISHER") "Altium Limited"))
      (libsource (lib "Miscellaneous Devices") (part "Cap Semi"))
    )
    (comp (ref "C143")
      (value "0.47uF")
      (footprint "CAPC1005L")
      (description "Capacitor (Semiconductor SIM Model)")
      (fields (field (name "PUBLISHER") "Altium Limited"))
      (libsource (lib "Miscellaneous Devices") (part "Cap Semi"))
    )
    (comp (ref "C144")
      (value "0.47uF")
      (footprint "CAPC1005L")
      (description "Capacitor (Semiconductor SIM Model)")
      (fields (field (name "PUBLISHER") "Altium Limited"))
      (libsource (lib "Miscellaneous Devices") (part "Cap Semi"))
    )
    (comp (ref "C145")
      (value "0.47uF")
      (footprint "CAPC1005L")
      (description "Capacitor (Semiconductor SIM Model)")
      (fields (field (name "PUBLISHER") "Altium Limited"))
      (libsource (lib "Miscellaneous Devices") (part "Cap Semi"))
    )
    (comp (ref "C154")
      (value "27pF")
      (footprint "CAPC1005L")
      (description "Capacitor (Semiconductor SIM Model)")
      (fields (field (name "PUBLISHER") "Altium Limited"))
      (libsource (lib "Miscellaneous Devices") (part "Cap Semi"))
    )
    (comp (ref "C_CK") (value "TP") (footprint "TP") (libsource (lib "S6") (part "TP")))
    (comp (ref "M1")
      (value "MB")
      (footprint "RESC1005L")
      (fields (field (name "PUBLISHER") "Altium Limited"))
      (libsource (lib "Miscellaneous Devices") (part "Res3"))
    )
    (comp (ref "M2")
      (value "MB")
      (footprint "RESC1005L")
      (fields (field (name "PUBLISHER") "Altium Limited"))
      (libsource (lib "Miscellaneous Devices") (part "Res3"))
    )
    (comp (ref "M3")
      (value "MB")
      (footprint "RESC1005L")
      (fields (field (name "PUBLISHER") "Altium Limited"))
      (libsource (lib "Miscellaneous Devices") (part "Res3"))
    )
    (comp (ref "M4")
      (value "MB")
      (footprint "RESC1005L")
      (fields (field (name "PUBLISHER") "Altium Limited"))
      (libsource (lib "Miscellaneous Devices") (part "Res3"))
    )
    (comp (ref "M5")
      (value "MB")
      (footprint "RESC1005L")
      (fields (field (name "PUBLISHER") "Altium Limited"))
      (libsource (lib "Miscellaneous Devices") (part "Res3"))
    )
    (comp (ref "M6")
      (value "MB")
      (footprint "RESC1005L")
      (fields (field (name "PUBLISHER") "Altium Limited"))
      (libsource (lib "Miscellaneous Devices") (part "Res3"))
    )
    (comp (ref "M7")
      (value "MB")
      (footprint "RESC1005L")
      (fields (field (name "PUBLISHER") "Altium Limited"))
      (libsource (lib "Miscellaneous Devices") (part "Res3"))
    )
    (comp (ref "M8")
      (value "MB")
      (footprint "RESC1005L")
      (fields (field (name "PUBLISHER") "Altium Limited"))
      (libsource (lib "Miscellaneous Devices") (part "Res3"))
    )
    (comp (ref "M10")
      (value "MB")
      (footprint "RESC1005L")
      (fields (field (name "PUBLISHER") "Altium Limited"))
      (libsource (lib "Miscellaneous Devices") (part "Res3"))
    )
    (comp (ref "M11")
      (value "MB")
      (footprint "RESC1005L")
      (fields (field (name "PUBLISHER") "Altium Limited"))
      (libsource (lib "Miscellaneous Devices") (part "Res3"))
    )
    (comp (ref "P1")
      (value "Header 10X2")
      (footprint "20PINSMT")
      (description "Header, 10-Pin, Dual row")
      (fields (field (name "PUBLISHER") "Altium Limited"))
      (libsource (lib "Miscellaneous Connectors") (part "Header 10X2"))
    )
    (comp (ref "R12")
      (value "100K")
      (footprint "RESC1005L")
      (description "Resistor")
      (fields (field (name "PUBLISHER") "Altium Limited"))
      (libsource (lib "Miscellaneous Devices") (part "Res3"))
    )
    (comp (ref "R13")
      (value "100K")
      (footprint "RESC1005L")
      (description "Resistor")
      (fields (field (name "PUBLISHER") "Altium Limited"))
      (libsource (lib "Miscellaneous Devices") (part "Res3"))
    )
    (comp (ref "R14")
      (value "100K")
      (footprint "RESC1005L")
      (description "Resistor")
      (fields (field (name "PUBLISHER") "Altium Limited"))
      (libsource (lib "Miscellaneous Devices") (part "Res3"))
    )
    (comp (ref "R15")
      (value "100K")
      (footprint "RESC1005L")
      (description "Resistor")
      (fields (field (name "PUBLISHER") "Altium Limited"))
      (libsource (lib "Miscellaneous Devices") (part "Res3"))
    )
    (comp (ref "R16")
      (value "100K")
      (footprint "RESC1005L")
      (description "Resistor")
      (fields (field (name "PUBLISHER") "Altium Limited"))
      (libsource (lib "Miscellaneous Devices") (part "Res3"))
    )
    (comp (ref "R17")
      (value "100K")
      (footprint "RESC1005L")
      (description "Resistor")
      (fields (field (name "PUBLISHER") "Altium Limited"))
      (libsource (lib "Miscellaneous Devices") (part "Res3"))
    )
    (comp (ref "R18")
      (value "100K")
      (footprint "RESC1005L")
      (description "Resistor")
      (fields (field (name "PUBLISHER") "Altium Limited"))
      (libsource (lib "Miscellaneous Devices") (part "Res3"))
    )
    (comp (ref "R19")
      (value "100K")
      (footprint "RESC1005L")
      (description "Resistor")
      (fields (field (name "PUBLISHER") "Altium Limited"))
      (libsource (lib "Miscellaneous Devices") (part "Res3"))
    )
    (comp (ref "R20")
      (value "100K")
      (footprint "RESC1005L")
      (description "Resistor")
      (fields (field (name "PUBLISHER") "Altium Limited"))
      (libsource (lib "Miscellaneous Devices") (part "Res3"))
    )
    (comp (ref "R21")
      (value "100K")
      (footprint "RESC1005L")
      (description "Resistor")
      (fields (field (name "PUBLISHER") "Altium Limited"))
      (libsource (lib "Miscellaneous Devices") (part "Res3"))
    )
    (comp (ref "R22")
      (value "2.2M")
      (footprint "RESC1005L")
      (description "Resistor")
      (fields (field (name "PUBLISHER") "Altium Limited"))
      (libsource (lib "Miscellaneous Devices") (part "Res3"))
    )
    (comp (ref "R23")
      (value "470R")
      (footprint "RESC1005L")
      (description "Resistor")
      (fields (field (name "PUBLISHER") "Altium Limited"))
      (libsource (lib "Miscellaneous Devices") (part "Res3"))
    )
    (comp (ref "R24")
      (value "470R")
      (footprint "RESC1005L")
      (description "Resistor")
      (fields (field (name "PUBLISHER") "Altium Limited"))
      (libsource (lib "Miscellaneous Devices") (part "Res3"))
    )
    (comp (ref "R25")
      (value "NC")
      (footprint "RESC1005L")
      (description "Resistor")
      (fields (field (name "PUBLISHER") "Altium Limited"))
      (libsource (lib "Miscellaneous Devices") (part "Res3"))
    )
    (comp (ref "R26")
      (value "0R")
      (footprint "RESC1005L")
      (description "Resistor")
      (fields (field (name "PUBLISHER") "Altium Limited"))
      (libsource (lib "Miscellaneous Devices") (part "Res3"))
    )
    (comp (ref "R27")
      (value "0R")
      (footprint "RESC1005L")
      (description "Resistor")
      (fields (field (name "PUBLISHER") "Altium Limited"))
      (libsource (lib "Miscellaneous Devices") (part "Res3"))
    )
    (comp (ref "R28")
      (value "1K")
      (footprint "RESC1005L")
      (description "Resistor")
      (fields (field (name "PUBLISHER") "Altium Limited"))
      (libsource (lib "Miscellaneous Devices") (part "Res3"))
    )
    (comp (ref "R29")
      (value "100R")
      (footprint "RESC1005L")
      (description "Resistor")
      (fields (field (name "PUBLISHER") "Altium Limited"))
      (libsource (lib "Miscellaneous Devices") (part "Res3"))
    )
    (comp (ref "R30")
      (value "100R")
      (footprint "RESC1005L")
      (description "Resistor")
      (fields (field (name "PUBLISHER") "Altium Limited"))
      (libsource (lib "Miscellaneous Devices") (part "Res3"))
    )
    (comp (ref "U3")
      (value "A3255")
      (footprint "QFN50P700X700-48V4N")
      (description "A3255 55nm mining chip")
      (libsource (lib "avalon_all") (part "A3255"))
    )
    (comp (ref "U4")
      (value "A3255")
      (footprint "QFN50P700X700-48V4N")
      (description "A3255 55nm mining chip")
      (libsource (lib "avalon_all") (part "A3255"))
    )
    (comp (ref "U5")
      (value "A3255")
      (footprint "QFN50P700X700-48V4N")
      (description "A3255 55nm mining chip")
      (libsource (lib "avalon_all") (part "A3255"))
    )
    (comp (ref "U6")
      (value "A3255")
      (footprint "QFN50P700X700-48V4N")
      (description "A3255 55nm mining chip")
      (libsource (lib "avalon_all") (part "A3255"))
    )
    (comp (ref "U7")
      (value "A3255")
      (footprint "QFN50P700X700-48V4N")
      (description "A3255 55nm mining chip")
      (libsource (lib "avalon_all") (part "A3255"))
    )
    (comp (ref "U8")
      (value "A3255")
      (footprint "QFN50P700X700-48V4N")
      (description "A3255 55nm mining chip")
      (libsource (lib "avalon_all") (part "A3255"))
    )
    (comp (ref "U9")
      (value "A3255")
      (footprint "QFN50P700X700-48V4N")
      (description "A3255 55nm mining chip")
      (libsource (lib "avalon_all") (part "A3255"))
    )
    (comp (ref "U10")
      (value "A3255")
      (footprint "QFN50P700X700-48V4N")
      (description "A3255 55nm mining chip")
      (libsource (lib "avalon_all") (part "A3255"))
    )
    (comp (ref "U11")
      (value "A3255")
      (footprint "QFN50P700X700-48V4N")
      (description "A3255 55nm mining chip")
      (libsource (lib "avalon_all") (part "A3255"))
    )
    (comp (ref "U12")
      (value "A3255")
      (footprint "QFN50P700X700-48V4N")
      (description "A3255 55nm mining chip")
      (libsource (lib "avalon_all") (part "A3255"))
    )
    (comp (ref "U13") (value "74LVC2G34") (footprint "SOT363_L") (libsource (lib "S6_2") (part "74LVC2G34")))
    (comp (ref "U14") (value "74LVC2G34") (footprint "SOT363_L") (libsource (lib "") (part "74LVC2G34_1")))
    (comp (ref "U15")
      (value "74HC2GU04")
      (footprint "SOT363_L")
      (description "Dual unbuffered inverter")
      (libsource (lib "avalon_all") (part "74HC2GU04"))
    )
    (comp (ref "U16")
      (value "74HC2GU04")
      (footprint "SOT363_L")
      (description "Dual unbuffered inverter")
      (libsource (lib "avalon_all") (part "74HC2GU04"))
    )
    (comp (ref "Y1")
      (value "XTAL_25M")
      (footprint "4SMX")
      (description "Crystal Oscillator")
      (fields (field (name "PUBLISHER") "Altium Limited"))
      (libsource (lib "avalon_all") (part "XTAL"))
    )
  )
  (nets
    (net (code "1") (name "/AVCC1V2") (class "Default")
      (node (ref "M1") (pin "2") (pinfunction "2_2") (pintype "passive"))
      (node (ref "M10") (pin "2") (pinfunction "2_2") (pintype "passive"))
      (node (ref "M11") (pin "2") (pinfunction "2_2") (pintype "passive"))
      (node (ref "M2") (pin "2") (pinfunction "2_2") (pintype "passive"))
      (node (ref "M3") (pin "2") (pinfunction "2_2") (pintype "passive"))
      (node (ref "M4") (pin "2") (pinfunction "2_2") (pintype "passive"))
      (node (ref "M5") (pin "2") (pinfunction "2_2") (pintype "passive"))
      (node (ref "M6") (pin "2") (pinfunction "2_2") (pintype "passive"))
      (node (ref "M7") (pin "2") (pinfunction "2_2") (pintype "passive"))
      (node (ref "M8") (pin "2") (pinfunction "2_2") (pintype "passive"))
    )
    (net (code "2") (name "/CLK") (class "Default")
      (node (ref "R25") (pin "2") (pinfunction "2_2") (pintype "passive"))
      (node (ref "U15") (pin "1") (pinfunction "1A_1") (pintype "input"))
      (node (ref "U16") (pin "6") (pinfunction "1Y_6") (pintype "output"))
    )
    (net (code "3") (name "/CLK_CONNECT") (class "Default")
      (node (ref "R25") (pin "1") (pinfunction "1_1") (pintype "passive"))
    )
    (net (code "4") (name "/CONFIG_N") (class "Default")
      (node (ref "U14") (pin "4") (pinfunction "2Y_4") (pintype "output"))
      (node (ref "U3") (pin "2") (pinfunction "CONFIG_NI_2") (pintype "input"))
    )
    (net (code "5") (name "/CONFIG_NO1") (class "Default")
      (node (ref "U3") (pin "35") (pinfunction "CONFIG_NO_35") (pintype "output"))
      (node (ref "U4") (pin "2") (pinfunction "CONFIG_NI_2") (pintype "input"))
    )
    (net (code "6") (name "/CONFIG_NO2") (class "Default")
      (node (ref "U4") (pin "35") (pinfunction "CONFIG_NO_35") (pintype "output"))
      (node (ref "U5") (pin "2") (pinfunction "CONFIG_NI_2") (pintype "input"))
    )
    (net (code "7") (name "/CONFIG_NO3") (class "Default")
      (node (ref "U5") (pin "35") (pinfunction "CONFIG_NO_35") (pintype "output"))
      (node (ref "U6") (pin "2") (pinfunction "CONFIG_NI_2") (pintype "input"))
    )
    (net (code "8") (name "/CONFIG_NO4") (class "Default")
      (node (ref "U6") (pin "35") (pinfunction "CONFIG_NO_35") (pintype "output"))
      (node (ref "U7") (pin "2") (pinfunction "CONFIG_NI_2") (pintype "input"))
    )
    (net (code "9") (name "/CONFIG_NO5") (class "Default")
      (node (ref "U7") (pin "35") (pinfunction "CONFIG_NO_35") (pintype "output"))
      (node (ref "U8") (pin "2") (pinfunction "CONFIG_NI_2") (pintype "input"))
    )
    (net (code "10") (name "/CONFIG_NO6") (class "Default")
      (node (ref "U8") (pin "35") (pinfunction "CONFIG_NO_35") (pintype "output"))
      (node (ref "U9") (pin "2") (pinfunction "CONFIG_NI_2") (pintype "input"))
    )
    (net (code "11") (name "/CONFIG_NO7") (class "Default")
      (node (ref "U10") (pin "2") (pinfunction "CONFIG_NI_2") (pintype "input"))
      (node (ref "U9") (pin "35") (pinfunction "CONFIG_NO_35") (pintype "output"))
    )
    (net (code "12") (name "/CONFIG_NO8") (class "Default")
      (node (ref "U10") (pin "35") (pinfunction "CONFIG_NO_35") (pintype "output"))
      (node (ref "U11") (pin "2") (pinfunction "CONFIG_NI_2") (pintype "input"))
    )
    (net (code "13") (name "/CONFIG_NO9") (class "Default")
      (node (ref "U11") (pin "35") (pinfunction "CONFIG_NO_35") (pintype "output"))
      (node (ref "U12") (pin "2") (pinfunction "CONFIG_NI_2") (pintype "input"))
    )
    (net (code "14") (name "/CONFIG_NO10") (class "Default")
      (node (ref "U12") (pin "35") (pinfunction "CONFIG_NO_35") (pintype "output"))
    )
    (net (code "15") (name "/CONFIG_P") (class "Default")
      (node (ref "U14") (pin "6") (pinfunction "1Y_6") (pintype "output"))
      (node (ref "U3") (pin "1") (pinfunction "CONFIG_PI_1") (pintype "input"))
    )
    (net (code "16") (name "/CONFIG_PO1") (class "Default")
      (node (ref "U3") (pin "36") (pinfunction "CONFIG_PO_36") (pintype "output"))
      (node (ref "U4") (pin "1") (pinfunction "CONFIG_PI_1") (pintype "input"))
    )
    (net (code "17") (name "/CONFIG_PO2") (class "Default")
      (node (ref "U4") (pin "36") (pinfunction "CONFIG_PO_36") (pintype "output"))
      (node (ref "U5") (pin "1") (pinfunction "CONFIG_PI_1") (pintype "input"))
    )
    (net (code "18") (name "/CONFIG_PO3") (class "Default")
      (node (ref "U5") (pin "36") (pinfunction "CONFIG_PO_36") (pintype "output"))
      (node (ref "U6") (pin "1") (pinfunction "CONFIG_PI_1") (pintype "input"))
    )
    (net (code "19") (name "/CONFIG_PO4") (class "Default")
      (node (ref "U6") (pin "36") (pinfunction "CONFIG_PO_36") (pintype "output"))
      (node (ref "U7") (pin "1") (pinfunction "CONFIG_PI_1") (pintype "input"))
    )
    (net (code "20") (name "/CONFIG_PO5") (class "Default")
      (node (ref "U7") (pin "36") (pinfunction "CONFIG_PO_36") (pintype "output"))
      (node (ref "U8") (pin "1") (pinfunction "CONFIG_PI_1") (pintype "input"))
    )
    (net (code "21") (name "/CONFIG_PO6") (class "Default")
      (node (ref "U8") (pin "36") (pinfunction "CONFIG_PO_36") (pintype "output"))
      (node (ref "U9") (pin "1") (pinfunction "CONFIG_PI_1") (pintype "input"))
    )
    (net (code "22") (name "/CONFIG_PO7") (class "Default")
      (node (ref "U10") (pin "1") (pinfunction "CONFIG_PI_1") (pintype "input"))
      (node (ref "U9") (pin "36") (pinfunction "CONFIG_PO_36") (pintype "output"))
    )
    (net (code "23") (name "/CONFIG_PO8") (class "Default")
      (node (ref "U10") (pin "36") (pinfunction "CONFIG_PO_36") (pintype "output"))
      (node (ref "U11") (pin "1") (pinfunction "CONFIG_PI_1") (pintype "input"))
    )
    (net (code "24") (name "/CONFIG_PO9") (class "Default")
      (node (ref "U11") (pin "36") (pinfunction "CONFIG_PO_36") (pintype "output"))
      (node (ref "U12") (pin "1") (pinfunction "CONFIG_PI_1") (pintype "input"))
    )
    (net (code "25") (name "/CONFIG_PO10") (class "Default")
      (node (ref "U12") (pin "36") (pinfunction "CONFIG_PO_36") (pintype "output"))
    )
    (net (code "26") (name "/C_CLK_OUT") (class "Default")
      (node (ref "C_CK") (pin "1") (pinfunction "TP_1") (pintype "passive"))
      (node (ref "U7") (pin "43") (pinfunction "C_CLKOUT_43") (pintype "output"))
    )
    (net (code "27") (name "/REPORT_N") (class "Default")
      (node (ref "R24") (pin "1") (pinfunction "1_1") (pintype "passive"))
      (node (ref "U10") (pin "16") (pinfunction "REPORT_N_16") (pintype "open_collector"))
      (node (ref "U11") (pin "16") (pinfunction "REPORT_N_16") (pintype "open_collector"))
      (node (ref "U12") (pin "16") (pinfunction "REPORT_N_16") (pintype "open_collector"))
      (node (ref "U13") (pin "3") (pinfunction "2A_3") (pintype "input"))
      (node (ref "U3") (pin "16") (pinfunction "REPORT_N_16") (pintype "open_collector"))
      (node (ref "U4") (pin "16") (pinfunction "REPORT_N_16") (pintype "open_collector"))
      (node (ref "U5") (pin "16") (pinfunction "REPORT_N_16") (pintype "open_collector"))
      (node (ref "U6") (pin "16") (pinfunction "REPORT_N_16") (pintype "open_collector"))
      (node (ref "U7") (pin "16") (pinfunction "REPORT_N_16") (pintype "open_collector"))
      (node (ref "U8") (pin "16") (pinfunction "REPORT_N_16") (pintype "open_collector"))
      (node (ref "U9") (pin "16") (pinfunction "REPORT_N_16") (pintype "open_collector"))
    )
    (net (code "28") (name "/REPORT_P") (class "Default")
      (node (ref "R23") (pin "1") (pinfunction "1_1") (pintype "passive"))
      (node (ref "U10") (pin "17") (pinfunction "REPORT_P_17") (pintype "open_collector"))
      (node (ref "U11") (pin "17") (pinfunction "REPORT_P_17") (pintype "open_collector"))
      (node (ref "U12") (pin "17") (pinfunction "REPORT_P_17") (pintype "open_collector"))
      (node (ref "U13") (pin "1") (pinfunction "1A_1") (pintype "input"))
      (node (ref "U3") (pin "17") (pinfunction "REPORT_P_17") (pintype "open_collector"))
      (node (ref "U4") (pin "17") (pinfunction "REPORT_P_17") (pintype "open_collector"))
      (node (ref "U5") (pin "17") (pinfunction "REPORT_P_17") (pintype "open_collector"))
      (node (ref "U6") (pin "17") (pinfunction "REPORT_P_17") (pintype "open_collector"))
      (node (ref "U7") (pin "17") (pinfunction "REPORT_P_17") (pintype "open_collector"))
      (node (ref "U8") (pin "17") (pinfunction "REPORT_P_17") (pintype "open_collector"))
      (node (ref "U9") (pin "17") (pinfunction "REPORT_P_17") (pintype "open_collector"))
    )
    (net (code "29") (name "/VCC1V2") (class "Default")
      (node (ref "C100") (pin "2") (pinfunction "2_2") (pintype "passive"))
      (node (ref "C101") (pin "2") (pinfunction "2_2") (pintype "passive"))
      (node (ref "C102") (pin "1") (pinfunction "1_1") (pintype "passive"))
      (node (ref "C103") (pin "1") (pinfunction "1_1") (pintype "passive"))
      (node (ref "C104") (pin "1") (pinfunction "1_1") (pintype "passive"))
      (node (ref "C105") (pin "1") (pinfunction "1_1") (pintype "passive"))
      (node (ref "C106") (pin "2") (pinfunction "2_2") (pintype "passive"))
      (node (ref "C107") (pin "2") (pinfunction "2_2") (pintype "passive"))
      (node (ref "C109") (pin "2") (pinfunction "2_2") (pintype "passive"))
      (node (ref "C110") (pin "2") (pinfunction "2_2") (pintype "passive"))
      (node (ref "C112") (pin "2") (pinfunction "2_2") (pintype "passive"))
      (node (ref "C113") (pin "2") (pinfunction "2_2") (pintype "passive"))
      (node (ref "C115") (pin "2") (pinfunction "2_2") (pintype "passive"))
      (node (ref "C116") (pin "2") (pinfunction "2_2") (pintype "passive"))
      (node (ref "C120") (pin "1") (pinfunction "1_1") (pintype "passive"))
      (node (ref "C121") (pin "2") (pinfunction "2_2") (pintype "passive"))
      (node (ref "C122") (pin "1") (pinfunction "1_1") (pintype "passive"))
      (node (ref "C123") (pin "2") (pinfunction "2_2") (pintype "passive"))
      (node (ref "C128") (pin "1") (pinfunction "1_1") (pintype "passive"))
      (node (ref "C129") (pin "2") (pinfunction "2_2") (pintype "passive"))
      (node (ref "C130") (pin "1") (pinfunction "1_1") (pintype "passive"))
      (node (ref "C131") (pin "2") (pinfunction "2_2") (pintype "passive"))
      (node (ref "C135") (pin "2") (pinfunction "2_2") (pintype "passive"))
      (node (ref "C136") (pin "2") (pinfunction "2_2") (pintype "passive"))
      (node (ref "C138") (pin "1") (pinfunction "1_1") (pintype "passive"))
      (node (ref "C139") (pin "1") (pinfunction "1_1") (pintype "passive"))
      (node (ref "C140") (pin "2") (pinfunction "2_2") (pintype "passive"))
      (node (ref "C141") (pin "2") (pinfunction "2_2") (pintype "passive"))
      (node (ref "C143") (pin "2") (pinfunction "2_2") (pintype "passive"))
      (node (ref "C144") (pin "2") (pinfunction "2_2") (pintype "passive"))
      (node (ref "C26") (pin "1") (pinfunction "1_1") (pintype "passive"))
      (node (ref "C27") (pin "2") (pinfunction "2_2") (pintype "passive"))
      (node (ref "C28") (pin "1") (pinfunction "1_1") (pintype "passive"))
      (node (ref "C29") (pin "2") (pinfunction "2_2") (pintype "passive"))
      (node (ref "C30") (pin "1") (pinfunction "1_1") (pintype "passive"))
      (node (ref "C31") (pin "2") (pinfunction "2_2") (pintype "passive"))
      (node (ref "C32") (pin "1") (pinfunction "1_1") (pintype "passive"))
      (node (ref "C33") (pin "2") (pinfunction "2_2") (pintype "passive"))
      (node (ref "C38") (pin "1") (pinfunction "1_1") (pintype "passive"))
      (node (ref "C39") (pin "2") (pinfunction "2_2") (pintype "passive"))
      (node (ref "C40") (pin "1") (pinfunction "1_1") (pintype "passive"))
      (node (ref "C41") (pin "2") (pinfunction "2_2") (pintype "passive"))
      (node (ref "C42") (pin "1") (pinfunction "1_1") (pintype "passive"))
      (node (ref "C43") (pin "2") (pinfunction "2_2") (pintype "passive"))
      (node (ref "C44") (pin "1") (pinfunction "1_1") (pintype "passive"))
      (node (ref "C45") (pin "2") (pinfunction "2_2") (pintype "passive"))
      (node (ref "C50") (pin "2") (pinfunction "2_2") (pintype "passive"))
      (node (ref "C51") (pin "2") (pinfunction "2_2") (pintype "passive"))
      (node (ref "C52") (pin "2") (pinfunction "2_2") (pintype "passive"))
      (node (ref "C53") (pin "2") (pinfunction "2_2") (pintype "passive"))
      (node (ref "C54") (pin "1") (pinfunction "1_1") (pintype "passive"))
      (node (ref "C55") (pin "1") (pinfunction "1_1") (pintype "passive"))
      (node (ref "C56") (pin "1") (pinfunction "1_1") (pintype "passive"))
      (node (ref "C57") (pin "1") (pinfunction "1_1") (pintype "passive"))
      (node (ref "C58") (pin "2") (pinfunction "2_2") (pintype "passive"))
      (node (ref "C59") (pin "2") (pinfunction "2_2") (pintype "passive"))
      (node (ref "C61") (pin "2") (pinfunction "2_2") (pintype "passive"))
      (node (ref "C62") (pin "2") (pinfunction "2_2") (pintype "passive"))
      (node (ref "C64") (pin "2") (pinfunction "2_2") (pintype "passive"))
      (node (ref "C65") (pin "2") (pinfunction "2_2") (pintype "passive"))
      (node (ref "C67") (pin "2") (pinfunction "2_2") (pintype "passive"))
      (node (ref "C68") (pin "2") (pinfunction "2_2") (pintype "passive"))
      (node (ref "C74") (pin "1") (pinfunction "1_1") (pintype "passive"))
      (node (ref "C75") (pin "2") (pinfunction "2_2") (pintype "passive"))
      (node (ref "C76") (pin "1") (pinfunction "1_1") (pintype "passive"))
      (node (ref "C77") (pin "2") (pinfunction "2_2") (pintype "passive"))
      (node (ref "C78") (pin "1") (pinfunction "1_1") (pintype "passive"))
      (node (ref "C79") (pin "2") (pinfunction "2_2") (pintype "passive"))
      (node (ref "C80") (pin "1") (pinfunction "1_1") (pintype "passive"))
      (node (ref "C81") (pin "2") (pinfunction "2_2") (pintype "passive"))
      (node (ref "C86") (pin "1") (pinfunction "1_1") (pintype "passive"))
      (node (ref "C87") (pin "2") (pinfunction "2_2") (pintype "passive"))
      (node (ref "C88") (pin "1") (pinfunction "1_1") (pintype "passive"))
      (node (ref "C89") (pin "2") (pinfunction "2_2") (pintype "passive"))
      (node (ref "C90") (pin "1") (pinfunction "1_1") (pintype "passive"))
      (node (ref "C91") (pin "2") (pinfunction "2_2") (pintype "passive"))
      (node (ref "C92") (pin "1") (pinfunction "1_1") (pintype "passive"))
      (node (ref "C93") (pin "2") (pinfunction "2_2") (pintype "passive"))
      (node (ref "C98") (pin "2") (pinfunction "2_2") (pintype "passive"))
      (node (ref "C99") (pin "2") (pinfunction "2_2") (pintype "passive"))
      (node (ref "U10") (pin "10") (pinfunction "VCC_10") (pintype "power_in"))
      (node (ref "U10") (pin "11") (pinfunction "VCC_11") (pintype "power_in"))
      (node (ref "U10") (pin "13") (pinfunction "VCC_13") (pintype "power_in"))
      (node (ref "U10") (pin "14") (pinfunction "VCC_14") (pintype "power_in"))
      (node (ref "U10") (pin "15") (pinfunction "VCC_15") (pintype "power_in"))
      (node (ref "U10") (pin "18") (pinfunction "VCC_18") (pintype "power_in"))
      (node (ref "U10") (pin "19") (pinfunction "VCC_19") (pintype "power_in"))
      (node (ref "U10") (pin "20") (pinfunction "VCC_20") (pintype "power_in"))
      (node (ref "U10") (pin "21") (pinfunction "VCC_21") (pintype "power_in"))
      (node (ref "U10") (pin "22") (pinfunction "VCC_22") (pintype "power_in"))
      (node (ref "U10") (pin "25") (pinfunction "VCC_25") (pintype "power_in"))
      (node (ref "U10") (pin "26") (pinfunction "VCC_26") (pintype "power_in"))
      (node (ref "U10") (pin "28") (pinfunction "VCC_28") (pintype "power_in"))
      (node (ref "U10") (pin "29") (pinfunction "VCC_29") (pintype "power_in"))
      (node (ref "U10") (pin "3") (pinfunction "VCC_3") (pintype "power_in"))
      (node (ref "U10") (pin "30") (pinfunction "VCC_30") (pintype "power_in"))
      (node (ref "U10") (pin "31") (pinfunction "VCC_31") (pintype "power_in"))
      (node (ref "U10") (pin "32") (pinfunction "VCC_32") (pintype "power_in"))
      (node (ref "U10") (pin "33") (pinfunction "VCC_33") (pintype "power_in"))
      (node (ref "U10") (pin "34") (pinfunction "VCC_34") (pintype "power_in"))
      (node (ref "U10") (pin "39") (pinfunction "VCC_39") (pintype "power_in"))
      (node (ref "U10") (pin "4") (pinfunction "VCC_4") (pintype "power_in"))
      (node (ref "U10") (pin "40") (pinfunction "VCC_40") (pintype "power_in"))
      (node (ref "U10") (pin "41") (pinfunction "VCC_41") (pintype "power_in"))
      (node (ref "U10") (pin "42") (pinfunction "VCC_42") (pintype "power_in"))
      (node (ref "U10") (pin "45") (pinfunction "VCC_45") (pintype "power_in"))
      (node (ref "U10") (pin "46") (pinfunction "VCC_46") (pintype "power_in"))
      (node (ref "U10") (pin "47") (pinfunction "VCC_47") (pintype "power_in"))
      (node (ref "U10") (pin "48") (pinfunction "VCC_48") (pintype "power_in"))
      (node (ref "U11") (pin "10") (pinfunction "VCC_10") (pintype "power_in"))
      (node (ref "U11") (pin "11") (pinfunction "VCC_11") (pintype "power_in"))
      (node (ref "U11") (pin "13") (pinfunction "VCC_13") (pintype "power_in"))
      (node (ref "U11") (pin "14") (pinfunction "VCC_14") (pintype "power_in"))
      (node (ref "U11") (pin "15") (pinfunction "VCC_15") (pintype "power_in"))
      (node (ref "U11") (pin "18") (pinfunction "VCC_18") (pintype "power_in"))
      (node (ref "U11") (pin "19") (pinfunction "VCC_19") (pintype "power_in"))
      (node (ref "U11") (pin "20") (pinfunction "VCC_20") (pintype "power_in"))
      (node (ref "U11") (pin "21") (pinfunction "VCC_21") (pintype "power_in"))
      (node (ref "U11") (pin "22") (pinfunction "VCC_22") (pintype "power_in"))
      (node (ref "U11") (pin "25") (pinfunction "VCC_25") (pintype "power_in"))
      (node (ref "U11") (pin "26") (pinfunction "VCC_26") (pintype "power_in"))
      (node (ref "U11") (pin "28") (pinfunction "VCC_28") (pintype "power_in"))
      (node (ref "U11") (pin "29") (pinfunction "VCC_29") (pintype "power_in"))
      (node (ref "U11") (pin "3") (pinfunction "VCC_3") (pintype "power_in"))
      (node (ref "U11") (pin "30") (pinfunction "VCC_30") (pintype "power_in"))
      (node (ref "U11") (pin "31") (pinfunction "VCC_31") (pintype "power_in"))
      (node (ref "U11") (pin "32") (pinfunction "VCC_32") (pintype "power_in"))
      (node (ref "U11") (pin "33") (pinfunction "VCC_33") (pintype "power_in"))
      (node (ref "U11") (pin "34") (pinfunction "VCC_34") (pintype "power_in"))
      (node (ref "U11") (pin "39") (pinfunction "VCC_39") (pintype "power_in"))
      (node (ref "U11") (pin "4") (pinfunction "VCC_4") (pintype "power_in"))
      (node (ref "U11") (pin "40") (pinfunction "VCC_40") (pintype "power_in"))
      (node (ref "U11") (pin "41") (pinfunction "VCC_41") (pintype "power_in"))
      (node (ref "U11") (pin "42") (pinfunction "VCC_42") (pintype "power_in"))
      (node (ref "U11") (pin "45") (pinfunction "VCC_45") (pintype "power_in"))
      (node (ref "U11") (pin "46") (pinfunction "VCC_46") (pintype "power_in"))
      (node (ref "U11") (pin "47") (pinfunction "VCC_47") (pintype "power_in"))
      (node (ref "U11") (pin "48") (pinfunction "VCC_48") (pintype "power_in"))
      (node (ref "U12") (pin "10") (pinfunction "VCC_10") (pintype "power_in"))
      (node (ref "U12") (pin "11") (pinfunction "VCC_11") (pintype "power_in"))
      (node (ref "U12") (pin "13") (pinfunction "VCC_13") (pintype "power_in"))
      (node (ref "U12") (pin "14") (pinfunction "VCC_14") (pintype "power_in"))
      (node (ref "U12") (pin "15") (pinfunction "VCC_15") (pintype "power_in"))
      (node (ref "U12") (pin "18") (pinfunction "VCC_18") (pintype "power_in"))
      (node (ref "U12") (pin "19") (pinfunction "VCC_19") (pintype "power_in"))
      (node (ref "U12") (pin "20") (pinfunction "VCC_20") (pintype "power_in"))
      (node (ref "U12") (pin "21") (pinfunction "VCC_21") (pintype "power_in"))
      (node (ref "U12") (pin "22") (pinfunction "VCC_22") (pintype "power_in"))
      (node (ref "U12") (pin "25") (pinfunction "VCC_25") (pintype "power_in"))
      (node (ref "U12") (pin "26") (pinfunction "VCC_26") (pintype "power_in"))
      (node (ref "U12") (pin "28") (pinfunction "VCC_28") (pintype "power_in"))
      (node (ref "U12") (pin "29") (pinfunction "VCC_29") (pintype "power_in"))
      (node (ref "U12") (pin "3") (pinfunction "VCC_3") (pintype "power_in"))
      (node (ref "U12") (pin "30") (pinfunction "VCC_30") (pintype "power_in"))
      (node (ref "U12") (pin "31") (pinfunction "VCC_31") (pintype "power_in"))
      (node (ref "U12") (pin "32") (pinfunction "VCC_32") (pintype "power_in"))
      (node (ref "U12") (pin "33") (pinfunction "VCC_33") (pintype "power_in"))
      (node (ref "U12") (pin "34") (pinfunction "VCC_34") (pintype "power_in"))
      (node (ref "U12") (pin "39") (pinfunction "VCC_39") (pintype "power_in"))
      (node (ref "U12") (pin "4") (pinfunction "VCC_4") (pintype "power_in"))
      (node (ref "U12") (pin "40") (pinfunction "VCC_40") (pintype "power_in"))
      (node (ref "U12") (pin "41") (pinfunction "VCC_41") (pintype "power_in"))
      (node (ref "U12") (pin "42") (pinfunction "VCC_42") (pintype "power_in"))
      (node (ref "U12") (pin "45") (pinfunction "VCC_45") (pintype "power_in"))
      (node (ref "U12") (pin "46") (pinfunction "VCC_46") (pintype "power_in"))
      (node (ref "U12") (pin "47") (pinfunction "VCC_47") (pintype "power_in"))
      (node (ref "U12") (pin "48") (pinfunction "VCC_48") (pintype "power_in"))
      (node (ref "U3") (pin "10") (pinfunction "VCC_10") (pintype "power_in"))
      (node (ref "U3") (pin "11") (pinfunction "VCC_11") (pintype "power_in"))
      (node (ref "U3") (pin "13") (pinfunction "VCC_13") (pintype "power_in"))
      (node (ref "U3") (pin "14") (pinfunction "VCC_14") (pintype "power_in"))
      (node (ref "U3") (pin "15") (pinfunction "VCC_15") (pintype "power_in"))
      (node (ref "U3") (pin "18") (pinfunction "VCC_18") (pintype "power_in"))
      (node (ref "U3") (pin "19") (pinfunction "VCC_19") (pintype "power_in"))
      (node (ref "U3") (pin "20") (pinfunction "VCC_20") (pintype "power_in"))
      (node (ref "U3") (pin "21") (pinfunction "VCC_21") (pintype "power_in"))
      (node (ref "U3") (pin "22") (pinfunction "VCC_22") (pintype "power_in"))
      (node (ref "U3") (pin "25") (pinfunction "VCC_25") (pintype "power_in"))
      (node (ref "U3") (pin "26") (pinfunction "VCC_26") (pintype "power_in"))
      (node (ref "U3") (pin "28") (pinfunction "VCC_28") (pintype "power_in"))
      (node (ref "U3") (pin "29") (pinfunction "VCC_29") (pintype "power_in"))
      (node (ref "U3") (pin "3") (pinfunction "VCC_3") (pintype "power_in"))
      (node (ref "U3") (pin "30") (pinfunction "VCC_30") (pintype "power_in"))
      (node (ref "U3") (pin "31") (pinfunction "VCC_31") (pintype "power_in"))
      (node (ref "U3") (pin "32") (pinfunction "VCC_32") (pintype "power_in"))
      (node (ref "U3") (pin "33") (pinfunction "VCC_33") (pintype "power_in"))
      (node (ref "U3") (pin "34") (pinfunction "VCC_34") (pintype "power_in"))
      (node (ref "U3") (pin "39") (pinfunction "VCC_39") (pintype "power_in"))
      (node (ref "U3") (pin "4") (pinfunction "VCC_4") (pintype "power_in"))
      (node (ref "U3") (pin "40") (pinfunction "VCC_40") (pintype "power_in"))
      (node (ref "U3") (pin "41") (pinfunction "VCC_41") (pintype "power_in"))
      (node (ref "U3") (pin "42") (pinfunction "VCC_42") (pintype "power_in"))
      (node (ref "U3") (pin "45") (pinfunction "VCC_45") (pintype "power_in"))
      (node (ref "U3") (pin "46") (pinfunction "VCC_46") (pintype "power_in"))
      (node (ref "U3") (pin "47") (pinfunction "VCC_47") (pintype "power_in"))
      (node (ref "U3") (pin "48") (pinfunction "VCC_48") (pintype "power_in"))
      (node (ref "U4") (pin "10") (pinfunction "VCC_10") (pintype "power_in"))
      (node (ref "U4") (pin "11") (pinfunction "VCC_11") (pintype "power_in"))
      (node (ref "U4") (pin "13") (pinfunction "VCC_13") (pintype "power_in"))
      (node (ref "U4") (pin "14") (pinfunction "VCC_14") (pintype "power_in"))
      (node (ref "U4") (pin "15") (pinfunction "VCC_15") (pintype "power_in"))
      (node (ref "U4") (pin "18") (pinfunction "VCC_18") (pintype "power_in"))
      (node (ref "U4") (pin "19") (pinfunction "VCC_19") (pintype "power_in"))
      (node (ref "U4") (pin "20") (pinfunction "VCC_20") (pintype "power_in"))
      (node (ref "U4") (pin "21") (pinfunction "VCC_21") (pintype "power_in"))
      (node (ref "U4") (pin "22") (pinfunction "VCC_22") (pintype "power_in"))
      (node (ref "U4") (pin "25") (pinfunction "VCC_25") (pintype "power_in"))
      (node (ref "U4") (pin "26") (pinfunction "VCC_26") (pintype "power_in"))
      (node (ref "U4") (pin "28") (pinfunction "VCC_28") (pintype "power_in"))
      (node (ref "U4") (pin "29") (pinfunction "VCC_29") (pintype "power_in"))
      (node (ref "U4") (pin "3") (pinfunction "VCC_3") (pintype "power_in"))
      (node (ref "U4") (pin "30") (pinfunction "VCC_30") (pintype "power_in"))
      (node (ref "U4") (pin "31") (pinfunction "VCC_31") (pintype "power_in"))
      (node (ref "U4") (pin "32") (pinfunction "VCC_32") (pintype "power_in"))
      (node (ref "U4") (pin "33") (pinfunction "VCC_33") (pintype "power_in"))
      (node (ref "U4") (pin "34") (pinfunction "VCC_34") (pintype "power_in"))
      (node (ref "U4") (pin "39") (pinfunction "VCC_39") (pintype "power_in"))
      (node (ref "U4") (pin "4") (pinfunction "VCC_4") (pintype "power_in"))
      (node (ref "U4") (pin "40") (pinfunction "VCC_40") (pintype "power_in"))
      (node (ref "U4") (pin "41") (pinfunction "VCC_41") (pintype "power_in"))
      (node (ref "U4") (pin "42") (pinfunction "VCC_42") (pintype "power_in"))
      (node (ref "U4") (pin "45") (pinfunction "VCC_45") (pintype "power_in"))
      (node (ref "U4") (pin "46") (pinfunction "VCC_46") (pintype "power_in"))
      (node (ref "U4") (pin "47") (pinfunction "VCC_47") (pintype "power_in"))
      (node (ref "U4") (pin "48") (pinfunction "VCC_48") (pintype "power_in"))
      (node (ref "U5") (pin "10") (pinfunction "VCC_10") (pintype "power_in"))
      (node (ref "U5") (pin "11") (pinfunction "VCC_11") (pintype "power_in"))
      (node (ref "U5") (pin "13") (pinfunction "VCC_13") (pintype "power_in"))
      (node (ref "U5") (pin "14") (pinfunction "VCC_14") (pintype "power_in"))
      (node (ref "U5") (pin "15") (pinfunction "VCC_15") (pintype "power_in"))
      (node (ref "U5") (pin "18") (pinfunction "VCC_18") (pintype "power_in"))
      (node (ref "U5") (pin "19") (pinfunction "VCC_19") (pintype "power_in"))
      (node (ref "U5") (pin "20") (pinfunction "VCC_20") (pintype "power_in"))
      (node (ref "U5") (pin "21") (pinfunction "VCC_21") (pintype "power_in"))
      (node (ref "U5") (pin "22") (pinfunction "VCC_22") (pintype "power_in"))
      (node (ref "U5") (pin "25") (pinfunction "VCC_25") (pintype "power_in"))
      (node (ref "U5") (pin "26") (pinfunction "VCC_26") (pintype "power_in"))
      (node (ref "U5") (pin "28") (pinfunction "VCC_28") (pintype "power_in"))
      (node (ref "U5") (pin "29") (pinfunction "VCC_29") (pintype "power_in"))
      (node (ref "U5") (pin "3") (pinfunction "VCC_3") (pintype "power_in"))
      (node (ref "U5") (pin "30") (pinfunction "VCC_30") (pintype "power_in"))
      (node (ref "U5") (pin "31") (pinfunction "VCC_31") (pintype "power_in"))
      (node (ref "U5") (pin "32") (pinfunction "VCC_32") (pintype "power_in"))
      (node (ref "U5") (pin "33") (pinfunction "VCC_33") (pintype "power_in"))
      (node (ref "U5") (pin "34") (pinfunction "VCC_34") (pintype "power_in"))
      (node (ref "U5") (pin "39") (pinfunction "VCC_39") (pintype "power_in"))
      (node (ref "U5") (pin "4") (pinfunction "VCC_4") (pintype "power_in"))
      (node (ref "U5") (pin "40") (pinfunction "VCC_40") (pintype "power_in"))
      (node (ref "U5") (pin "41") (pinfunction "VCC_41") (pintype "power_in"))
      (node (ref "U5") (pin "42") (pinfunction "VCC_42") (pintype "power_in"))
      (node (ref "U5") (pin "45") (pinfunction "VCC_45") (pintype "power_in"))
      (node (ref "U5") (pin "46") (pinfunction "VCC_46") (pintype "power_in"))
      (node (ref "U5") (pin "47") (pinfunction "VCC_47") (pintype "power_in"))
      (node (ref "U5") (pin "48") (pinfunction "VCC_48") (pintype "power_in"))
      (node (ref "U6") (pin "10") (pinfunction "VCC_10") (pintype "power_in"))
      (node (ref "U6") (pin "11") (pinfunction "VCC_11") (pintype "power_in"))
      (node (ref "U6") (pin "13") (pinfunction "VCC_13") (pintype "power_in"))
      (node (ref "U6") (pin "14") (pinfunction "VCC_14") (pintype "power_in"))
      (node (ref "U6") (pin "15") (pinfunction "VCC_15") (pintype "power_in"))
      (node (ref "U6") (pin "18") (pinfunction "VCC_18") (pintype "power_in"))
      (node (ref "U6") (pin "19") (pinfunction "VCC_19") (pintype "power_in"))
      (node (ref "U6") (pin "20") (pinfunction "VCC_20") (pintype "power_in"))
      (node (ref "U6") (pin "21") (pinfunction "VCC_21") (pintype "power_in"))
      (node (ref "U6") (pin "22") (pinfunction "VCC_22") (pintype "power_in"))
      (node (ref "U6") (pin "25") (pinfunction "VCC_25") (pintype "power_in"))
      (node (ref "U6") (pin "26") (pinfunction "VCC_26") (pintype "power_in"))
      (node (ref "U6") (pin "28") (pinfunction "VCC_28") (pintype "power_in"))
      (node (ref "U6") (pin "29") (pinfunction "VCC_29") (pintype "power_in"))
      (node (ref "U6") (pin "3") (pinfunction "VCC_3") (pintype "power_in"))
      (node (ref "U6") (pin "30") (pinfunction "VCC_30") (pintype "power_in"))
      (node (ref "U6") (pin "31") (pinfunction "VCC_31") (pintype "power_in"))
      (node (ref "U6") (pin "32") (pinfunction "VCC_32") (pintype "power_in"))
      (node (ref "U6") (pin "33") (pinfunction "VCC_33") (pintype "power_in"))
      (node (ref "U6") (pin "34") (pinfunction "VCC_34") (pintype "power_in"))
      (node (ref "U6") (pin "39") (pinfunction "VCC_39") (pintype "power_in"))
      (node (ref "U6") (pin "4") (pinfunction "VCC_4") (pintype "power_in"))
      (node (ref "U6") (pin "40") (pinfunction "VCC_40") (pintype "power_in"))
      (node (ref "U6") (pin "41") (pinfunction "VCC_41") (pintype "power_in"))
      (node (ref "U6") (pin "42") (pinfunction "VCC_42") (pintype "power_in"))
      (node (ref "U6") (pin "45") (pinfunction "VCC_45") (pintype "power_in"))
      (node (ref "U6") (pin "46") (pinfunction "VCC_46") (pintype "power_in"))
      (node (ref "U6") (pin "47") (pinfunction "VCC_47") (pintype "power_in"))
      (node (ref "U6") (pin "48") (pinfunction "VCC_48") (pintype "power_in"))
      (node (ref "U7") (pin "10") (pinfunction "VCC_10") (pintype "power_in"))
      (node (ref "U7") (pin "11") (pinfunction "VCC_11") (pintype "power_in"))
      (node (ref "U7") (pin "13") (pinfunction "VCC_13") (pintype "power_in"))
      (node (ref "U7") (pin "14") (pinfunction "VCC_14") (pintype "power_in"))
      (node (ref "U7") (pin "15") (pinfunction "VCC_15") (pintype "power_in"))
      (node (ref "U7") (pin "18") (pinfunction "VCC_18") (pintype "power_in"))
      (node (ref "U7") (pin "19") (pinfunction "VCC_19") (pintype "power_in"))
      (node (ref "U7") (pin "20") (pinfunction "VCC_20") (pintype "power_in"))
      (node (ref "U7") (pin "21") (pinfunction "VCC_21") (pintype "power_in"))
      (node (ref "U7") (pin "22") (pinfunction "VCC_22") (pintype "power_in"))
      (node (ref "U7") (pin "25") (pinfunction "VCC_25") (pintype "power_in"))
      (node (ref "U7") (pin "26") (pinfunction "VCC_26") (pintype "power_in"))
      (node (ref "U7") (pin "28") (pinfunction "VCC_28") (pintype "power_in"))
      (node (ref "U7") (pin "29") (pinfunction "VCC_29") (pintype "power_in"))
      (node (ref "U7") (pin "3") (pinfunction "VCC_3") (pintype "power_in"))
      (node (ref "U7") (pin "30") (pinfunction "VCC_30") (pintype "power_in"))
      (node (ref "U7") (pin "31") (pinfunction "VCC_31") (pintype "power_in"))
      (node (ref "U7") (pin "32") (pinfunction "VCC_32") (pintype "power_in"))
      (node (ref "U7") (pin "33") (pinfunction "VCC_33") (pintype "power_in"))
      (node (ref "U7") (pin "34") (pinfunction "VCC_34") (pintype "power_in"))
      (node (ref "U7") (pin "39") (pinfunction "VCC_39") (pintype "power_in"))
      (node (ref "U7") (pin "4") (pinfunction "VCC_4") (pintype "power_in"))
      (node (ref "U7") (pin "40") (pinfunction "VCC_40") (pintype "power_in"))
      (node (ref "U7") (pin "41") (pinfunction "VCC_41") (pintype "power_in"))
      (node (ref "U7") (pin "42") (pinfunction "VCC_42") (pintype "power_in"))
      (node (ref "U7") (pin "45") (pinfunction "VCC_45") (pintype "power_in"))
      (node (ref "U7") (pin "46") (pinfunction "VCC_46") (pintype "power_in"))
      (node (ref "U7") (pin "47") (pinfunction "VCC_47") (pintype "power_in"))
      (node (ref "U7") (pin "48") (pinfunction "VCC_48") (pintype "power_in"))
      (node (ref "U8") (pin "10") (pinfunction "VCC_10") (pintype "power_in"))
      (node (ref "U8") (pin "11") (pinfunction "VCC_11") (pintype "power_in"))
      (node (ref "U8") (pin "13") (pinfunction "VCC_13") (pintype "power_in"))
      (node (ref "U8") (pin "14") (pinfunction "VCC_14") (pintype "power_in"))
      (node (ref "U8") (pin "15") (pinfunction "VCC_15") (pintype "power_in"))
      (node (ref "U8") (pin "18") (pinfunction "VCC_18") (pintype "power_in"))
      (node (ref "U8") (pin "19") (pinfunction "VCC_19") (pintype "power_in"))
      (node (ref "U8") (pin "20") (pinfunction "VCC_20") (pintype "power_in"))
      (node (ref "U8") (pin "21") (pinfunction "VCC_21") (pintype "power_in"))
      (node (ref "U8") (pin "22") (pinfunction "VCC_22") (pintype "power_in"))
      (node (ref "U8") (pin "25") (pinfunction "VCC_25") (pintype "power_in"))
      (node (ref "U8") (pin "26") (pinfunction "VCC_26") (pintype "power_in"))
      (node (ref "U8") (pin "28") (pinfunction "VCC_28") (pintype "power_in"))
      (node (ref "U8") (pin "29") (pinfunction "VCC_29") (pintype "power_in"))
      (node (ref "U8") (pin "3") (pinfunction "VCC_3") (pintype "power_in"))
      (node (ref "U8") (pin "30") (pinfunction "VCC_30") (pintype "power_in"))
      (node (ref "U8") (pin "31") (pinfunction "VCC_31") (pintype "power_in"))
      (node (ref "U8") (pin "32") (pinfunction "VCC_32") (pintype "power_in"))
      (node (ref "U8") (pin "33") (pinfunction "VCC_33") (pintype "power_in"))
      (node (ref "U8") (pin "34") (pinfunction "VCC_34") (pintype "power_in"))
      (node (ref "U8") (pin "39") (pinfunction "VCC_39") (pintype "power_in"))
      (node (ref "U8") (pin "4") (pinfunction "VCC_4") (pintype "power_in"))
      (node (ref "U8") (pin "40") (pinfunction "VCC_40") (pintype "power_in"))
      (node (ref "U8") (pin "41") (pinfunction "VCC_41") (pintype "power_in"))
      (node (ref "U8") (pin "42") (pinfunction "VCC_42") (pintype "power_in"))
      (node (ref "U8") (pin "45") (pinfunction "VCC_45") (pintype "power_in"))
      (node (ref "U8") (pin "46") (pinfunction "VCC_46") (pintype "power_in"))
      (node (ref "U8") (pin "47") (pinfunction "VCC_47") (pintype "power_in"))
      (node (ref "U8") (pin "48") (pinfunction "VCC_48") (pintype "power_in"))
      (node (ref "U9") (pin "10") (pinfunction "VCC_10") (pintype "power_in"))
      (node (ref "U9") (pin "11") (pinfunction "VCC_11") (pintype "power_in"))
      (node (ref "U9") (pin "13") (pinfunction "VCC_13") (pintype "power_in"))
      (node (ref "U9") (pin "14") (pinfunction "VCC_14") (pintype "power_in"))
      (node (ref "U9") (pin "15") (pinfunction "VCC_15") (pintype "power_in"))
      (node (ref "U9") (pin "18") (pinfunction "VCC_18") (pintype "power_in"))
      (node (ref "U9") (pin "19") (pinfunction "VCC_19") (pintype "power_in"))
      (node (ref "U9") (pin "20") (pinfunction "VCC_20") (pintype "power_in"))
      (node (ref "U9") (pin "21") (pinfunction "VCC_21") (pintype "power_in"))
      (node (ref "U9") (pin "22") (pinfunction "VCC_22") (pintype "power_in"))
      (node (ref "U9") (pin "25") (pinfunction "VCC_25") (pintype "power_in"))
      (node (ref "U9") (pin "26") (pinfunction "VCC_26") (pintype "power_in"))
      (node (ref "U9") (pin "28") (pinfunction "VCC_28") (pintype "power_in"))
      (node (ref "U9") (pin "29") (pinfunction "VCC_29") (pintype "power_in"))
      (node (ref "U9") (pin "3") (pinfunction "VCC_3") (pintype "power_in"))
      (node (ref "U9") (pin "30") (pinfunction "VCC_30") (pintype "power_in"))
      (node (ref "U9") (pin "31") (pinfunction "VCC_31") (pintype "power_in"))
      (node (ref "U9") (pin "32") (pinfunction "VCC_32") (pintype "power_in"))
      (node (ref "U9") (pin "33") (pinfunction "VCC_33") (pintype "power_in"))
      (node (ref "U9") (pin "34") (pinfunction "VCC_34") (pintype "power_in"))
      (node (ref "U9") (pin "39") (pinfunction "VCC_39") (pintype "power_in"))
      (node (ref "U9") (pin "4") (pinfunction "VCC_4") (pintype "power_in"))
      (node (ref "U9") (pin "40") (pinfunction "VCC_40") (pintype "power_in"))
      (node (ref "U9") (pin "41") (pinfunction "VCC_41") (pintype "power_in"))
      (node (ref "U9") (pin "42") (pinfunction "VCC_42") (pintype "power_in"))
      (node (ref "U9") (pin "45") (pinfunction "VCC_45") (pintype "power_in"))
      (node (ref "U9") (pin "46") (pinfunction "VCC_46") (pintype "power_in"))
      (node (ref "U9") (pin "47") (pinfunction "VCC_47") (pintype "power_in"))
      (node (ref "U9") (pin "48") (pinfunction "VCC_48") (pintype "power_in"))
    )
    (net (code "30") (name "/VCC12V") (class "Default")
      (node (ref "P1") (pin "17") (pinfunction "17_17") (pintype "passive"))
      (node (ref "P1") (pin "18") (pinfunction "18_18") (pintype "passive"))
      (node (ref "P1") (pin "19") (pinfunction "19_19") (pintype "passive"))
      (node (ref "P1") (pin "20") (pinfunction "20_20") (pintype "passive"))
    )
    (net (code "31") (name "/XCLK1") (class "Default")
      (node (ref "R26") (pin "1") (pinfunction "1_1") (pintype "passive"))
      (node (ref "U3") (pin "9") (pinfunction "XCLK_IN_9") (pintype "input"))
      (node (ref "U4") (pin "9") (pinfunction "XCLK_IN_9") (pintype "input"))
      (node (ref "U5") (pin "9") (pinfunction "XCLK_IN_9") (pintype "input"))
      (node (ref "U6") (pin "9") (pinfunction "XCLK_IN_9") (pintype "input"))
      (node (ref "U7") (pin "9") (pinfunction "XCLK_IN_9") (pintype "input"))
    )
    (net (code "32") (name "/XCLK2") (class "Default")
      (node (ref "R27") (pin "1") (pinfunction "1_1") (pintype "passive"))
      (node (ref "U10") (pin "9") (pinfunction "XCLK_IN_9") (pintype "input"))
      (node (ref "U11") (pin "9") (pinfunction "XCLK_IN_9") (pintype "input"))
      (node (ref "U12") (pin "9") (pinfunction "XCLK_IN_9") (pintype "input"))
      (node (ref "U8") (pin "9") (pinfunction "XCLK_IN_9") (pintype "input"))
      (node (ref "U9") (pin "9") (pinfunction "XCLK_IN_9") (pintype "input"))
    )
    (net (code "33") (name "GND") (class "Default")
      (node (ref "C100") (pin "1") (pinfunction "1_1") (pintype "passive"))
      (node (ref "C101") (pin "1") (pinfunction "1_1") (pintype "passive"))
      (node (ref "C102") (pin "2") (pinfunction "2_2") (pintype "passive"))
      (node (ref "C103") (pin "2") (pinfunction "2_2") (pintype "passive"))
      (node (ref "C104") (pin "2") (pinfunction "2_2") (pintype "passive"))
      (node (ref "C105") (pin "2") (pinfunction "2_2") (pintype "passive"))
      (node (ref "C106") (pin "1") (pinfunction "1_1") (pintype "passive"))
      (node (ref "C107") (pin "1") (pinfunction "1_1") (pintype "passive"))
      (node (ref "C108") (pin "1") (pinfunction "1_1") (pintype "passive"))
      (node (ref "C109") (pin "1") (pinfunction "1_1") (pintype "passive"))
      (node (ref "C110") (pin "1") (pinfunction "1_1") (pintype "passive"))
      (node (ref "C111") (pin "1") (pinfunction "1_1") (pintype "passive"))
      (node (ref "C112") (pin "1") (pinfunction "1_1") (pintype "passive"))
      (node (ref "C113") (pin "1") (pinfunction "1_1") (pintype "passive"))
      (node (ref "C114") (pin "1") (pinfunction "1_1") (pintype "passive"))
      (node (ref "C115") (pin "1") (pinfunction "1_1") (pintype "passive"))
      (node (ref "C116") (pin "1") (pinfunction "1_1") (pintype "passive"))
      (node (ref "C117") (pin "1") (pinfunction "1_1") (pintype "passive"))
      (node (ref "C118") (pin "2") (pinfunction "2_2") (pintype "passive"))
      (node (ref "C119") (pin "2") (pinfunction "2_2") (pintype "passive"))
      (node (ref "C120") (pin "2") (pinfunction "2_2") (pintype "passive"))
      (node (ref "C121") (pin "1") (pinfunction "1_1") (pintype "passive"))
      (node (ref "C122") (pin "2") (pinfunction "2_2") (pintype "passive"))
      (node (ref "C123") (pin "1") (pinfunction "1_1") (pintype "passive"))
      (node (ref "C124") (pin "1") (pinfunction "1_1") (pintype "passive"))
      (node (ref "C125") (pin "1") (pinfunction "1_1") (pintype "passive"))
      (node (ref "C126") (pin "1") (pinfunction "1_1") (pintype "passive"))
      (node (ref "C127") (pin "1") (pinfunction "1_1") (pintype "passive"))
      (node (ref "C128") (pin "2") (pinfunction "2_2") (pintype "passive"))
      (node (ref "C129") (pin "1") (pinfunction "1_1") (pintype "passive"))
      (node (ref "C130") (pin "2") (pinfunction "2_2") (pintype "passive"))
      (node (ref "C131") (pin "1") (pinfunction "1_1") (pintype "passive"))
      (node (ref "C132") (pin "2") (pinfunction "2_2") (pintype "passive"))
      (node (ref "C133") (pin "2") (pinfunction "2_2") (pintype "passive"))
      (node (ref "C134") (pin "2") (pinfunction "2_2") (pintype "passive"))
      (node (ref "C135") (pin "1") (pinfunction "1_1") (pintype "passive"))
      (node (ref "C136") (pin "1") (pinfunction "1_1") (pintype "passive"))
      (node (ref "C137") (pin "2") (pinfunction "2_2") (pintype "passive"))
      (node (ref "C138") (pin "2") (pinfunction "2_2") (pintype "passive"))
      (node (ref "C139") (pin "2") (pinfunction "2_2") (pintype "passive"))
      (node (ref "C140") (pin "1") (pinfunction "1_1") (pintype "passive"))
      (node (ref "C141") (pin "1") (pinfunction "1_1") (pintype "passive"))
      (node (ref "C142") (pin "1") (pinfunction "1_1") (pintype "passive"))
      (node (ref "C143") (pin "1") (pinfunction "1_1") (pintype "passive"))
      (node (ref "C144") (pin "1") (pinfunction "1_1") (pintype "passive"))
      (node (ref "C145") (pin "1") (pinfunction "1_1") (pintype "passive"))
      (node (ref "C154") (pin "1") (pinfunction "1_1") (pintype "passive"))
      (node (ref "C22") (pin "2") (pinfunction "2_2") (pintype "passive"))
      (node (ref "C23") (pin "2") (pinfunction "2_2") (pintype "passive"))
      (node (ref "C24") (pin "2") (pinfunction "2_2") (pintype "passive"))
      (node (ref "C25") (pin "2") (pinfunction "2_2") (pintype "passive"))
      (node (ref "C26") (pin "2") (pinfunction "2_2") (pintype "passive"))
      (node (ref "C27") (pin "1") (pinfunction "1_1") (pintype "passive"))
      (node (ref "C28") (pin "2") (pinfunction "2_2") (pintype "passive"))
      (node (ref "C29") (pin "1") (pinfunction "1_1") (pintype "passive"))
      (node (ref "C30") (pin "2") (pinfunction "2_2") (pintype "passive"))
      (node (ref "C31") (pin "1") (pinfunction "1_1") (pintype "passive"))
      (node (ref "C32") (pin "2") (pinfunction "2_2") (pintype "passive"))
      (node (ref "C33") (pin "1") (pinfunction "1_1") (pintype "passive"))
      (node (ref "C34") (pin "1") (pinfunction "1_1") (pintype "passive"))
      (node (ref "C35") (pin "1") (pinfunction "1_1") (pintype "passive"))
      (node (ref "C36") (pin "1") (pinfunction "1_1") (pintype "passive"))
      (node (ref "C37") (pin "1") (pinfunction "1_1") (pintype "passive"))
      (node (ref "C38") (pin "2") (pinfunction "2_2") (pintype "passive"))
      (node (ref "C39") (pin "1") (pinfunction "1_1") (pintype "passive"))
      (node (ref "C40") (pin "2") (pinfunction "2_2") (pintype "passive"))
      (node (ref "C41") (pin "1") (pinfunction "1_1") (pintype "passive"))
      (node (ref "C42") (pin "2") (pinfunction "2_2") (pintype "passive"))
      (node (ref "C43") (pin "1") (pinfunction "1_1") (pintype "passive"))
      (node (ref "C44") (pin "2") (pinfunction "2_2") (pintype "passive"))
      (node (ref "C45") (pin "1") (pinfunction "1_1") (pintype "passive"))
      (node (ref "C46") (pin "2") (pinfunction "2_2") (pintype "passive"))
      (node (ref "C47") (pin "2") (pinfunction "2_2") (pintype "passive"))
      (node (ref "C48") (pin "2") (pinfunction "2_2") (pintype "passive"))
      (node (ref "C49") (pin "2") (pinfunction "2_2") (pintype "passive"))
      (node (ref "C50") (pin "1") (pinfunction "1_1") (pintype "passive"))
      (node (ref "C51") (pin "1") (pinfunction "1_1") (pintype "passive"))
      (node (ref "C52") (pin "1") (pinfunction "1_1") (pintype "passive"))
      (node (ref "C53") (pin "1") (pinfunction "1_1") (pintype "passive"))
      (node (ref "C54") (pin "2") (pinfunction "2_2") (pintype "passive"))
      (node (ref "C55") (pin "2") (pinfunction "2_2") (pintype "passive"))
      (node (ref "C56") (pin "2") (pinfunction "2_2") (pintype "passive"))
      (node (ref "C57") (pin "2") (pinfunction "2_2") (pintype "passive"))
      (node (ref "C58") (pin "1") (pinfunction "1_1") (pintype "passive"))
      (node (ref "C59") (pin "1") (pinfunction "1_1") (pintype "passive"))
      (node (ref "C60") (pin "1") (pinfunction "1_1") (pintype "passive"))
      (node (ref "C61") (pin "1") (pinfunction "1_1") (pintype "passive"))
      (node (ref "C62") (pin "1") (pinfunction "1_1") (pintype "passive"))
      (node (ref "C63") (pin "1") (pinfunction "1_1") (pintype "passive"))
      (node (ref "C64") (pin "1") (pinfunction "1_1") (pintype "passive"))
      (node (ref "C65") (pin "1") (pinfunction "1_1") (pintype "passive"))
      (node (ref "C66") (pin "1") (pinfunction "1_1") (pintype "passive"))
      (node (ref "C67") (pin "1") (pinfunction "1_1") (pintype "passive"))
      (node (ref "C68") (pin "1") (pinfunction "1_1") (pintype "passive"))
      (node (ref "C69") (pin "1") (pinfunction "1_1") (pintype "passive"))
      (node (ref "C70") (pin "2") (pinfunction "2_2") (pintype "passive"))
      (node (ref "C71") (pin "2") (pinfunction "2_2") (pintype "passive"))
      (node (ref "C72") (pin "2") (pinfunction "2_2") (pintype "passive"))
      (node (ref "C73") (pin "2") (pinfunction "2_2") (pintype "passive"))
      (node (ref "C74") (pin "2") (pinfunction "2_2") (pintype "passive"))
      (node (ref "C75") (pin "1") (pinfunction "1_1") (pintype "passive"))
      (node (ref "C76") (pin "2") (pinfunction "2_2") (pintype "passive"))
      (node (ref "C77") (pin "1") (pinfunction "1_1") (pintype "passive"))
      (node (ref "C78") (pin "2") (pinfunction "2_2") (pintype "passive"))
      (node (ref "C79") (pin "1") (pinfunction "1_1") (pintype "passive"))
      (node (ref "C80") (pin "2") (pinfunction "2_2") (pintype "passive"))
      (node (ref "C81") (pin "1") (pinfunction "1_1") (pintype "passive"))
      (node (ref "C82") (pin "1") (pinfunction "1_1") (pintype "passive"))
      (node (ref "C83") (pin "1") (pinfunction "1_1") (pintype "passive"))
      (node (ref "C84") (pin "1") (pinfunction "1_1") (pintype "passive"))
      (node (ref "C85") (pin "1") (pinfunction "1_1") (pintype "passive"))
      (node (ref "C86") (pin "2") (pinfunction "2_2") (pintype "passive"))
      (node (ref "C87") (pin "1") (pinfunction "1_1") (pintype "passive"))
      (node (ref "C88") (pin "2") (pinfunction "2_2") (pintype "passive"))
      (node (ref "C89") (pin "1") (pinfunction "1_1") (pintype "passive"))
      (node (ref "C90") (pin "2") (pinfunction "2_2") (pintype "passive"))
      (node (ref "C91") (pin "1") (pinfunction "1_1") (pintype "passive"))
      (node (ref "C92") (pin "2") (pinfunction "2_2") (pintype "passive"))
      (node (ref "C93") (pin "1") (pinfunction "1_1") (pintype "passive"))
      (node (ref "C94") (pin "2") (pinfunction "2_2") (pintype "passive"))
      (node (ref "C95") (pin "2") (pinfunction "2_2") (pintype "passive"))
      (node (ref "C96") (pin "2") (pinfunction "2_2") (pintype "passive"))
      (node (ref "C97") (pin "2") (pinfunction "2_2") (pintype "passive"))
      (node (ref "C98") (pin "1") (pinfunction "1_1") (pintype "passive"))
      (node (ref "C99") (pin "1") (pinfunction "1_1") (pintype "passive"))
      (node (ref "P1") (pin "11") (pinfunction "11_11") (pintype "passive"))
      (node (ref "P1") (pin "13") (pinfunction "13_13") (pintype "passive"))
      (node (ref "P1") (pin "15") (pinfunction "15_15") (pintype "passive"))
      (node (ref "P1") (pin "16") (pinfunction "16_16") (pintype "passive"))
      (node (ref "P1") (pin "3") (pinfunction "3_3") (pintype "passive"))
      (node (ref "P1") (pin "5") (pinfunction "5_5") (pintype "passive"))
      (node (ref "P1") (pin "7") (pinfunction "7_7") (pintype "passive"))
      (node (ref "P1") (pin "9") (pinfunction "9_9") (pintype "passive"))
      (node (ref "U10") (pin "12") (pinfunction "GND_12") (pintype "power_in"))
      (node (ref "U10") (pin "23") (pinfunction "GND_23") (pintype "power_in"))
      (node (ref "U10") (pin "27") (pinfunction "GND_27") (pintype "power_in"))
      (node (ref "U10") (pin "38") (pinfunction "GND_38") (pintype "power_in"))
      (node (ref "U10") (pin "49") (pinfunction "GND_49") (pintype "power_in"))
      (node (ref "U10") (pin "5") (pinfunction "AGND_PLL_5") (pintype "power_in"))
      (node (ref "U10") (pin "8") (pinfunction "GND_PLL_8") (pintype "power_in"))
      (node (ref "U11") (pin "12") (pinfunction "GND_12") (pintype "power_in"))
      (node (ref "U11") (pin "23") (pinfunction "GND_23") (pintype "power_in"))
      (node (ref "U11") (pin "27") (pinfunction "GND_27") (pintype "power_in"))
      (node (ref "U11") (pin "38") (pinfunction "GND_38") (pintype "power_in"))
      (node (ref "U11") (pin "49") (pinfunction "GND_49") (pintype "power_in"))
      (node (ref "U11") (pin "5") (pinfunction "AGND_PLL_5") (pintype "power_in"))
      (node (ref "U11") (pin "8") (pinfunction "GND_PLL_8") (pintype "power_in"))
      (node (ref "U12") (pin "12") (pinfunction "GND_12") (pintype "power_in"))
      (node (ref "U12") (pin "23") (pinfunction "GND_23") (pintype "power_in"))
      (node (ref "U12") (pin "27") (pinfunction "GND_27") (pintype "power_in"))
      (node (ref "U12") (pin "38") (pinfunction "GND_38") (pintype "power_in"))
      (node (ref "U12") (pin "49") (pinfunction "GND_49") (pintype "power_in"))
      (node (ref "U12") (pin "5") (pinfunction "AGND_PLL_5") (pintype "power_in"))
      (node (ref "U12") (pin "8") (pinfunction "GND_PLL_8") (pintype "power_in"))
      (node (ref "U13") (pin "2") (pinfunction "GND_2") (pintype "power_in"))
      (node (ref "U14") (pin "2") (pinfunction "GND_2") (pintype "power_in"))
      (node (ref "U15") (pin "2") (pinfunction "GND_2") (pintype "power_in"))
      (node (ref "U16") (pin "2") (pinfunction "GND_2") (pintype "power_in"))
      (node (ref "U3") (pin "12") (pinfunction "GND_12") (pintype "power_in"))
      (node (ref "U3") (pin "23") (pinfunction "GND_23") (pintype "power_in"))
      (node (ref "U3") (pin "27") (pinfunction "GND_27") (pintype "power_in"))
      (node (ref "U3") (pin "38") (pinfunction "GND_38") (pintype "power_in"))
      (node (ref "U3") (pin "49") (pinfunction "GND_49") (pintype "power_in"))
      (node (ref "U3") (pin "5") (pinfunction "AGND_PLL_5") (pintype "power_in"))
      (node (ref "U3") (pin "8") (pinfunction "GND_PLL_8") (pintype "power_in"))
      (node (ref "U4") (pin "12") (pinfunction "GND_12") (pintype "power_in"))
      (node (ref "U4") (pin "23") (pinfunction "GND_23") (pintype "power_in"))
      (node (ref "U4") (pin "27") (pinfunction "GND_27") (pintype "power_in"))
      (node (ref "U4") (pin "38") (pinfunction "GND_38") (pintype "power_in"))
      (node (ref "U4") (pin "49") (pinfunction "GND_49") (pintype "power_in"))
      (node (ref "U4") (pin "5") (pinfunction "AGND_PLL_5") (pintype "power_in"))
      (node (ref "U4") (pin "8") (pinfunction "GND_PLL_8") (pintype "power_in"))
      (node (ref "U5") (pin "12") (pinfunction "GND_12") (pintype "power_in"))
      (node (ref "U5") (pin "23") (pinfunction "GND_23") (pintype "power_in"))
      (node (ref "U5") (pin "27") (pinfunction "GND_27") (pintype "power_in"))
      (node (ref "U5") (pin "38") (pinfunction "GND_38") (pintype "power_in"))
      (node (ref "U5") (pin "49") (pinfunction "GND_49") (pintype "power_in"))
      (node (ref "U5") (pin "5") (pinfunction "AGND_PLL_5") (pintype "power_in"))
      (node (ref "U5") (pin "8") (pinfunction "GND_PLL_8") (pintype "power_in"))
      (node (ref "U6") (pin "12") (pinfunction "GND_12") (pintype "power_in"))
      (node (ref "U6") (pin "23") (pinfunction "GND_23") (pintype "power_in"))
      (node (ref "U6") (pin "27") (pinfunction "GND_27") (pintype "power_in"))
      (node (ref "U6") (pin "38") (pinfunction "GND_38") (pintype "power_in"))
      (node (ref "U6") (pin "49") (pinfunction "GND_49") (pintype "power_in"))
      (node (ref "U6") (pin "5") (pinfunction "AGND_PLL_5") (pintype "power_in"))
      (node (ref "U6") (pin "8") (pinfunction "GND_PLL_8") (pintype "power_in"))
      (node (ref "U7") (pin "12") (pinfunction "GND_12") (pintype "power_in"))
      (node (ref "U7") (pin "23") (pinfunction "GND_23") (pintype "power_in"))
      (node (ref "U7") (pin "27") (pinfunction "GND_27") (pintype "power_in"))
      (node (ref "U7") (pin "38") (pinfunction "GND_38") (pintype "power_in"))
      (node (ref "U7") (pin "49") (pinfunction "GND_49") (pintype "power_in"))
      (node (ref "U7") (pin "5") (pinfunction "AGND_PLL_5") (pintype "power_in"))
      (node (ref "U7") (pin "8") (pinfunction "GND_PLL_8") (pintype "power_in"))
      (node (ref "U8") (pin "12") (pinfunction "GND_12") (pintype "power_in"))
      (node (ref "U8") (pin "23") (pinfunction "GND_23") (pintype "power_in"))
      (node (ref "U8") (pin "27") (pinfunction "GND_27") (pintype "power_in"))
      (node (ref "U8") (pin "38") (pinfunction "GND_38") (pintype "power_in"))
      (node (ref "U8") (pin "49") (pinfunction "GND_49") (pintype "power_in"))
      (node (ref "U8") (pin "5") (pinfunction "AGND_PLL_5") (pintype "power_in"))
      (node (ref "U8") (pin "8") (pinfunction "GND_PLL_8") (pintype "power_in"))
      (node (ref "U9") (pin "12") (pinfunction "GND_12") (pintype "power_in"))
      (node (ref "U9") (pin "23") (pinfunction "GND_23") (pintype "power_in"))
      (node (ref "U9") (pin "27") (pinfunction "GND_27") (pintype "power_in"))
      (node (ref "U9") (pin "38") (pinfunction "GND_38") (pintype "power_in"))
      (node (ref "U9") (pin "49") (pinfunction "GND_49") (pintype "power_in"))
      (node (ref "U9") (pin "5") (pinfunction "AGND_PLL_5") (pintype "power_in"))
      (node (ref "U9") (pin "8") (pinfunction "GND_PLL_8") (pintype "power_in"))
    )
    (net (code "34") (name "Net-(P1-Pad8)") (class "Default")
      (node (ref "P1") (pin "8") (pinfunction "8_8") (pintype "passive"))
      (node (ref "R30") (pin "1") (pinfunction "1_1") (pintype "passive"))
    )
    (net (code "35") (name "Net-(P1-Pad10)") (class "Default")
      (node (ref "P1") (pin "10") (pinfunction "10_10") (pintype "passive"))
      (node (ref "R29") (pin "1") (pinfunction "1_1") (pintype "passive"))
    )
    (net (code "36") (name "Net-(U3-AVCC_PLL)") (class "Default")
      (node (ref "C46") (pin "1") (pinfunction "1_1") (pintype "passive"))
      (node (ref "M1") (pin "1") (pinfunction "1_1") (pintype "passive"))
      (node (ref "U3") (pin "6") (pinfunction "AVCC_PLL_6") (pintype "power_in"))
      (node (ref "U3") (pin "7") (pinfunction "VCC_PLL_7") (pintype "power_in"))
    )
    (net (code "37") (name "Net-(U3-RST_N)") (class "Default")
      (node (ref "C22") (pin "1") (pinfunction "1_1") (pintype "passive"))
      (node (ref "R12") (pin "1") (pinfunction "1_1") (pintype "passive"))
      (node (ref "U3") (pin "44") (pinfunction "RST_N_44") (pintype "input"))
    )
    (net (code "38") (name "Net-(U4-AVCC_PLL)") (class "Default")
      (node (ref "C47") (pin "1") (pinfunction "1_1") (pintype "passive"))
      (node (ref "M2") (pin "1") (pinfunction "1_1") (pintype "passive"))
      (node (ref "U4") (pin "6") (pinfunction "AVCC_PLL_6") (pintype "power_in"))
      (node (ref "U4") (pin "7") (pinfunction "VCC_PLL_7") (pintype "power_in"))
    )
    (net (code "39") (name "Net-(U4-RST_N)") (class "Default")
      (node (ref "C23") (pin "1") (pinfunction "1_1") (pintype "passive"))
      (node (ref "R13") (pin "1") (pinfunction "1_1") (pintype "passive"))
      (node (ref "U4") (pin "44") (pinfunction "RST_N_44") (pintype "input"))
    )
    (net (code "40") (name "Net-(U5-AVCC_PLL)") (class "Default")
      (node (ref "C48") (pin "1") (pinfunction "1_1") (pintype "passive"))
      (node (ref "M3") (pin "1") (pinfunction "1_1") (pintype "passive"))
      (node (ref "U5") (pin "6") (pinfunction "AVCC_PLL_6") (pintype "power_in"))
      (node (ref "U5") (pin "7") (pinfunction "VCC_PLL_7") (pintype "power_in"))
    )
    (net (code "41") (name "Net-(U5-RST_N)") (class "Default")
      (node (ref "C24") (pin "1") (pinfunction "1_1") (pintype "passive"))
      (node (ref "R14") (pin "1") (pinfunction "1_1") (pintype "passive"))
      (node (ref "U5") (pin "44") (pinfunction "RST_N_44") (pintype "input"))
    )
    (net (code "42") (name "Net-(U6-AVCC_PLL)") (class "Default")
      (node (ref "C49") (pin "1") (pinfunction "1_1") (pintype "passive"))
      (node (ref "M4") (pin "1") (pinfunction "1_1") (pintype "passive"))
      (node (ref "U6") (pin "6") (pinfunction "AVCC_PLL_6") (pintype "power_in"))
      (node (ref "U6") (pin "7") (pinfunction "VCC_PLL_7") (pintype "power_in"))
    )
    (net (code "43") (name "Net-(U6-RST_N)") (class "Default")
      (node (ref "C25") (pin "1") (pinfunction "1_1") (pintype "passive"))
      (node (ref "R15") (pin "1") (pinfunction "1_1") (pintype "passive"))
      (node (ref "U6") (pin "44") (pinfunction "RST_N_44") (pintype "input"))
    )
    (net (code "44") (name "Net-(U7-AVCC_PLL)") (class "Default")
      (node (ref "C94") (pin "1") (pinfunction "1_1") (pintype "passive"))
      (node (ref "M5") (pin "1") (pinfunction "1_1") (pintype "passive"))
      (node (ref "U7") (pin "6") (pinfunction "AVCC_PLL_6") (pintype "power_in"))
      (node (ref "U7") (pin "7") (pinfunction "VCC_PLL_7") (pintype "power_in"))
    )
    (net (code "45") (name "Net-(U7-RST_N)") (class "Default")
      (node (ref "C70") (pin "1") (pinfunction "1_1") (pintype "passive"))
      (node (ref "R16") (pin "1") (pinfunction "1_1") (pintype "passive"))
      (node (ref "U7") (pin "44") (pinfunction "RST_N_44") (pintype "input"))
    )
    (net (code "46") (name "Net-(U8-AVCC_PLL)") (class "Default")
      (node (ref "C95") (pin "1") (pinfunction "1_1") (pintype "passive"))
      (node (ref "M6") (pin "1") (pinfunction "1_1") (pintype "passive"))
      (node (ref "U8") (pin "6") (pinfunction "AVCC_PLL_6") (pintype "power_in"))
      (node (ref "U8") (pin "7") (pinfunction "VCC_PLL_7") (pintype "power_in"))
    )
    (net (code "47") (name "Net-(U8-RST_N)") (class "Default")
      (node (ref "C71") (pin "1") (pinfunction "1_1") (pintype "passive"))
      (node (ref "R17") (pin "1") (pinfunction "1_1") (pintype "passive"))
      (node (ref "U8") (pin "44") (pinfunction "RST_N_44") (pintype "input"))
    )
    (net (code "48") (name "Net-(U9-AVCC_PLL)") (class "Default")
      (node (ref "C96") (pin "1") (pinfunction "1_1") (pintype "passive"))
      (node (ref "M7") (pin "1") (pinfunction "1_1") (pintype "passive"))
      (node (ref "U9") (pin "6") (pinfunction "AVCC_PLL_6") (pintype "power_in"))
      (node (ref "U9") (pin "7") (pinfunction "VCC_PLL_7") (pintype "power_in"))
    )
    (net (code "49") (name "Net-(U9-RST_N)") (class "Default")
      (node (ref "C72") (pin "1") (pinfunction "1_1") (pintype "passive"))
      (node (ref "R18") (pin "1") (pinfunction "1_1") (pintype "passive"))
      (node (ref "U9") (pin "44") (pinfunction "RST_N_44") (pintype "input"))
    )
    (net (code "50") (name "Net-(U10-AVCC_PLL)") (class "Default")
      (node (ref "C97") (pin "1") (pinfunction "1_1") (pintype "passive"))
      (node (ref "M8") (pin "1") (pinfunction "1_1") (pintype "passive"))
      (node (ref "U10") (pin "6") (pinfunction "AVCC_PLL_6") (pintype "power_in"))
      (node (ref "U10") (pin "7") (pinfunction "VCC_PLL_7") (pintype "power_in"))
    )
    (net (code "51") (name "Net-(U10-RST_N)") (class "Default")
      (node (ref "C73") (pin "1") (pinfunction "1_1") (pintype "passive"))
      (node (ref "R19") (pin "1") (pinfunction "1_1") (pintype "passive"))
      (node (ref "U10") (pin "44") (pinfunction "RST_N_44") (pintype "input"))
    )
    (net (code "52") (name "Net-(U11-AVCC_PLL)") (class "Default")
      (node (ref "C133") (pin "1") (pinfunction "1_1") (pintype "passive"))
      (node (ref "M10") (pin "1") (pinfunction "1_1") (pintype "passive"))
      (node (ref "U11") (pin "6") (pinfunction "AVCC_PLL_6") (pintype "power_in"))
      (node (ref "U11") (pin "7") (pinfunction "VCC_PLL_7") (pintype "power_in"))
    )
    (net (code "53") (name "Net-(U11-RST_N)") (class "Default")
      (node (ref "C118") (pin "1") (pinfunction "1_1") (pintype "passive"))
      (node (ref "R20") (pin "1") (pinfunction "1_1") (pintype "passive"))
      (node (ref "U11") (pin "44") (pinfunction "RST_N_44") (pintype "input"))
    )
    (net (code "54") (name "Net-(U12-AVCC_PLL)") (class "Default")
      (node (ref "C134") (pin "1") (pinfunction "1_1") (pintype "passive"))
      (node (ref "M11") (pin "1") (pinfunction "1_1") (pintype "passive"))
      (node (ref "U12") (pin "6") (pinfunction "AVCC_PLL_6") (pintype "power_in"))
      (node (ref "U12") (pin "7") (pinfunction "VCC_PLL_7") (pintype "power_in"))
    )
    (net (code "55") (name "Net-(U12-RST_N)") (class "Default")
      (node (ref "C119") (pin "1") (pinfunction "1_1") (pintype "passive"))
      (node (ref "R21") (pin "1") (pinfunction "1_1") (pintype "passive"))
      (node (ref "U12") (pin "44") (pinfunction "RST_N_44") (pintype "input"))
    )
    (net (code "56") (name "Net-(U13-1Y)") (class "Default")
      (node (ref "R29") (pin "2") (pinfunction "2_2") (pintype "passive"))
      (node (ref "U13") (pin "6") (pinfunction "1Y_6") (pintype "output"))
    )
    (net (code "57") (name "Net-(U13-2Y)") (class "Default")
      (node (ref "R30") (pin "2") (pinfunction "2_2") (pintype "passive"))
      (node (ref "U13") (pin "4") (pinfunction "2Y_4") (pintype "output"))
    )
    (net (code "58") (name "Net-(U14-1A)") (class "Default")
      (node (ref "P1") (pin "4") (pinfunction "4_4") (pintype "passive"))
      (node (ref "U14") (pin "1") (pinfunction "1A_1") (pintype "input"))
    )
    (net (code "59") (name "Net-(U14-2A)") (class "Default")
      (node (ref "P1") (pin "6") (pinfunction "6_6") (pintype "passive"))
      (node (ref "U14") (pin "3") (pinfunction "2A_3") (pintype "input"))
    )
    (net (code "60") (name "Net-(U15-1Y)") (class "Default")
      (node (ref "R26") (pin "2") (pinfunction "2_2") (pintype "passive"))
      (node (ref "U15") (pin "3") (pinfunction "2A_3") (pintype "input"))
      (node (ref "U15") (pin "6") (pinfunction "1Y_6") (pintype "output"))
    )
    (net (code "61") (name "Net-(U15-2Y)") (class "Default")
      (node (ref "R27") (pin "2") (pinfunction "2_2") (pintype "passive"))
      (node (ref "U15") (pin "4") (pinfunction "2Y_4") (pintype "output"))
    )
    (net (code "62") (name "Net-(U16-1A)") (class "Default")
      (node (ref "C154") (pin "2") (pinfunction "2_2") (pintype "passive"))
      (node (ref "R22") (pin "2") (pinfunction "2_2") (pintype "passive"))
      (node (ref "U16") (pin "1") (pinfunction "1A_1") (pintype "input"))
      (node (ref "U16") (pin "3") (pinfunction "2A_3") (pintype "input"))
      (node (ref "Y1") (pin "1") (pinfunction "OSC1_1") (pintype "passive"))
    )
    (net (code "63") (name "Net-(U16-2Y)") (class "Default")
      (node (ref "R22") (pin "1") (pinfunction "1_1") (pintype "passive"))
      (node (ref "R28") (pin "1") (pinfunction "1_1") (pintype "passive"))
      (node (ref "U16") (pin "4") (pinfunction "2Y_4") (pintype "output"))
    )
    (net (code "64") (name "Net-(Y1-OSC2)") (class "Default")
      (node (ref "C127") (pin "2") (pinfunction "2_2") (pintype "passive"))
      (node (ref "R28") (pin "2") (pinfunction "2_2") (pintype "passive"))
      (node (ref "Y1") (pin "2") (pinfunction "OSC2_2") (pintype "passive"))
    )
    (net (code "65") (name "VCC3V3") (class "Default")
      (node (ref "C108") (pin "2") (pinfunction "2_2") (pintype "passive"))
      (node (ref "C111") (pin "2") (pinfunction "2_2") (pintype "passive"))
      (node (ref "C114") (pin "2") (pinfunction "2_2") (pintype "passive"))
      (node (ref "C117") (pin "2") (pinfunction "2_2") (pintype "passive"))
      (node (ref "C124") (pin "2") (pinfunction "2_2") (pintype "passive"))
      (node (ref "C125") (pin "2") (pinfunction "2_2") (pintype "passive"))
      (node (ref "C126") (pin "2") (pinfunction "2_2") (pintype "passive"))
      (node (ref "C132") (pin "1") (pinfunction "1_1") (pintype "passive"))
      (node (ref "C137") (pin "1") (pinfunction "1_1") (pintype "passive"))
      (node (ref "C142") (pin "2") (pinfunction "2_2") (pintype "passive"))
      (node (ref "C145") (pin "2") (pinfunction "2_2") (pintype "passive"))
      (node (ref "C34") (pin "2") (pinfunction "2_2") (pintype "passive"))
      (node (ref "C35") (pin "2") (pinfunction "2_2") (pintype "passive"))
      (node (ref "C36") (pin "2") (pinfunction "2_2") (pintype "passive"))
      (node (ref "C37") (pin "2") (pinfunction "2_2") (pintype "passive"))
      (node (ref "C60") (pin "2") (pinfunction "2_2") (pintype "passive"))
      (node (ref "C63") (pin "2") (pinfunction "2_2") (pintype "passive"))
      (node (ref "C66") (pin "2") (pinfunction "2_2") (pintype "passive"))
      (node (ref "C69") (pin "2") (pinfunction "2_2") (pintype "passive"))
      (node (ref "C82") (pin "2") (pinfunction "2_2") (pintype "passive"))
      (node (ref "C83") (pin "2") (pinfunction "2_2") (pintype "passive"))
      (node (ref "C84") (pin "2") (pinfunction "2_2") (pintype "passive"))
      (node (ref "C85") (pin "2") (pinfunction "2_2") (pintype "passive"))
      (node (ref "P1") (pin "1") (pinfunction "1_1") (pintype "passive"))
      (node (ref "P1") (pin "2") (pinfunction "2_2") (pintype "passive"))
      (node (ref "R12") (pin "2") (pinfunction "2_2") (pintype "passive"))
      (node (ref "R13") (pin "2") (pinfunction "2_2") (pintype "passive"))
      (node (ref "R14") (pin "2") (pinfunction "2_2") (pintype "passive"))
      (node (ref "R15") (pin "2") (pinfunction "2_2") (pintype "passive"))
      (node (ref "R16") (pin "2") (pinfunction "2_2") (pintype "passive"))
      (node (ref "R17") (pin "2") (pinfunction "2_2") (pintype "passive"))
      (node (ref "R18") (pin "2") (pinfunction "2_2") (pintype "passive"))
      (node (ref "R19") (pin "2") (pinfunction "2_2") (pintype "passive"))
      (node (ref "R20") (pin "2") (pinfunction "2_2") (pintype "passive"))
      (node (ref "R21") (pin "2") (pinfunction "2_2") (pintype "passive"))
      (node (ref "R23") (pin "2") (pinfunction "2_2") (pintype "passive"))
      (node (ref "R24") (pin "2") (pinfunction "2_2") (pintype "passive"))
      (node (ref "U10") (pin "24") (pinfunction "VCCIO_24") (pintype "power_in"))
      (node (ref "U10") (pin "37") (pinfunction "VCCIO_37") (pintype "power_in"))
      (node (ref "U11") (pin "24") (pinfunction "VCCIO_24") (pintype "power_in"))
      (node (ref "U11") (pin "37") (pinfunction "VCCIO_37") (pintype "power_in"))
      (node (ref "U12") (pin "24") (pinfunction "VCCIO_24") (pintype "power_in"))
      (node (ref "U12") (pin "37") (pinfunction "VCCIO_37") (pintype "power_in"))
      (node (ref "U13") (pin "5") (pinfunction "VCC_5") (pintype "power_in"))
      (node (ref "U14") (pin "5") (pinfunction "VCC_5") (pintype "power_in"))
      (node (ref "U15") (pin "5") (pinfunction "VCC_5") (pintype "power_in"))
      (node (ref "U16") (pin "5") (pinfunction "VCC_5") (pintype "power_in"))
      (node (ref "U3") (pin "24") (pinfunction "VCCIO_24") (pintype "power_in"))
      (node (ref "U3") (pin "37") (pinfunction "VCCIO_37") (pintype "power_in"))
      (node (ref "U4") (pin "24") (pinfunction "VCCIO_24") (pintype "power_in"))
      (node (ref "U4") (pin "37") (pinfunction "VCCIO_37") (pintype "power_in"))
      (node (ref "U5") (pin "24") (pinfunction "VCCIO_24") (pintype "power_in"))
      (node (ref "U5") (pin "37") (pinfunction "VCCIO_37") (pintype "power_in"))
      (node (ref "U6") (pin "24") (pinfunction "VCCIO_24") (pintype "power_in"))
      (node (ref "U6") (pin "37") (pinfunction "VCCIO_37") (pintype "power_in"))
      (node (ref "U7") (pin "24") (pinfunction "VCCIO_24") (pintype "power_in"))
      (node (ref "U7") (pin "37") (pinfunction "VCCIO_37") (pintype "power_in"))
      (node (ref "U8") (pin "24") (pinfunction "VCCIO_24") (pintype "power_in"))
      (node (ref "U8") (pin "37") (pinfunction "VCCIO_37") (pintype "power_in"))
      (node (ref "U9") (pin "24") (pinfunction "VCCIO_24") (pintype "power_in"))
      (node (ref "U9") (pin "37") (pinfunction "VCCIO_37") (pintype "power_in"))
    )
    (net (code "66") (name "unconnected-(P1-Pad12)") (class "Default")
      (node (ref "P1") (pin "12") (pinfunction "12_12") (pintype "passive"))
    )
    (net (code "67") (name "unconnected-(P1-Pad14)") (class "Default")
      (node (ref "P1") (pin "14") (pinfunction "14_14") (pintype "passive"))
    )
    (net (code "68") (name "unconnected-(U3-C_CLKOUT-Pad43)") (class "Default")
      (node (ref "U3") (pin "43") (pinfunction "C_CLKOUT_43") (pintype "output"))
    )
    (net (code "69") (name "unconnected-(U4-C_CLKOUT-Pad43)") (class "Default")
      (node (ref "U4") (pin "43") (pinfunction "C_CLKOUT_43") (pintype "output"))
    )
    (net (code "70") (name "unconnected-(U5-C_CLKOUT-Pad43)") (class "Default")
      (node (ref "U5") (pin "43") (pinfunction "C_CLKOUT_43") (pintype "output"))
    )
    (net (code "71") (name "unconnected-(U6-C_CLKOUT-Pad43)") (class "Default")
      (node (ref "U6") (pin "43") (pinfunction "C_CLKOUT_43") (pintype "output"))
    )
    (net (code "72") (name "unconnected-(U8-C_CLKOUT-Pad43)") (class "Default")
      (node (ref "U8") (pin "43") (pinfunction "C_CLKOUT_43") (pintype "output"))
    )
    (net (code "73") (name "unconnected-(U9-C_CLKOUT-Pad43)") (class "Default")
      (node (ref "U9") (pin "43") (pinfunction "C_CLKOUT_43") (pintype "output"))
    )
    (net (code "74") (name "unconnected-(U10-C_CLKOUT-Pad43)") (class "Default")
      (node (ref "U10") (pin "43") (pinfunction "C_CLKOUT_43") (pintype "output"))
    )
    (net (code "75") (name "unconnected-(U11-C_CLKOUT-Pad43)") (class "Default")
      (node (ref "U11") (pin "43") (pinfunction "C_CLKOUT_43") (pintype "output"))
    )
    (net (code "76") (name "unconnected-(U12-C_CLKOUT-Pad43)") (class "Default")
      (node (ref "U12") (pin "43") (pinfunction "C_CLKOUT_43") (pintype "output"))
    )
  )
)
